# oresat-c3-v2.net
KiCad netlist of a schematic drawn in EAGLE
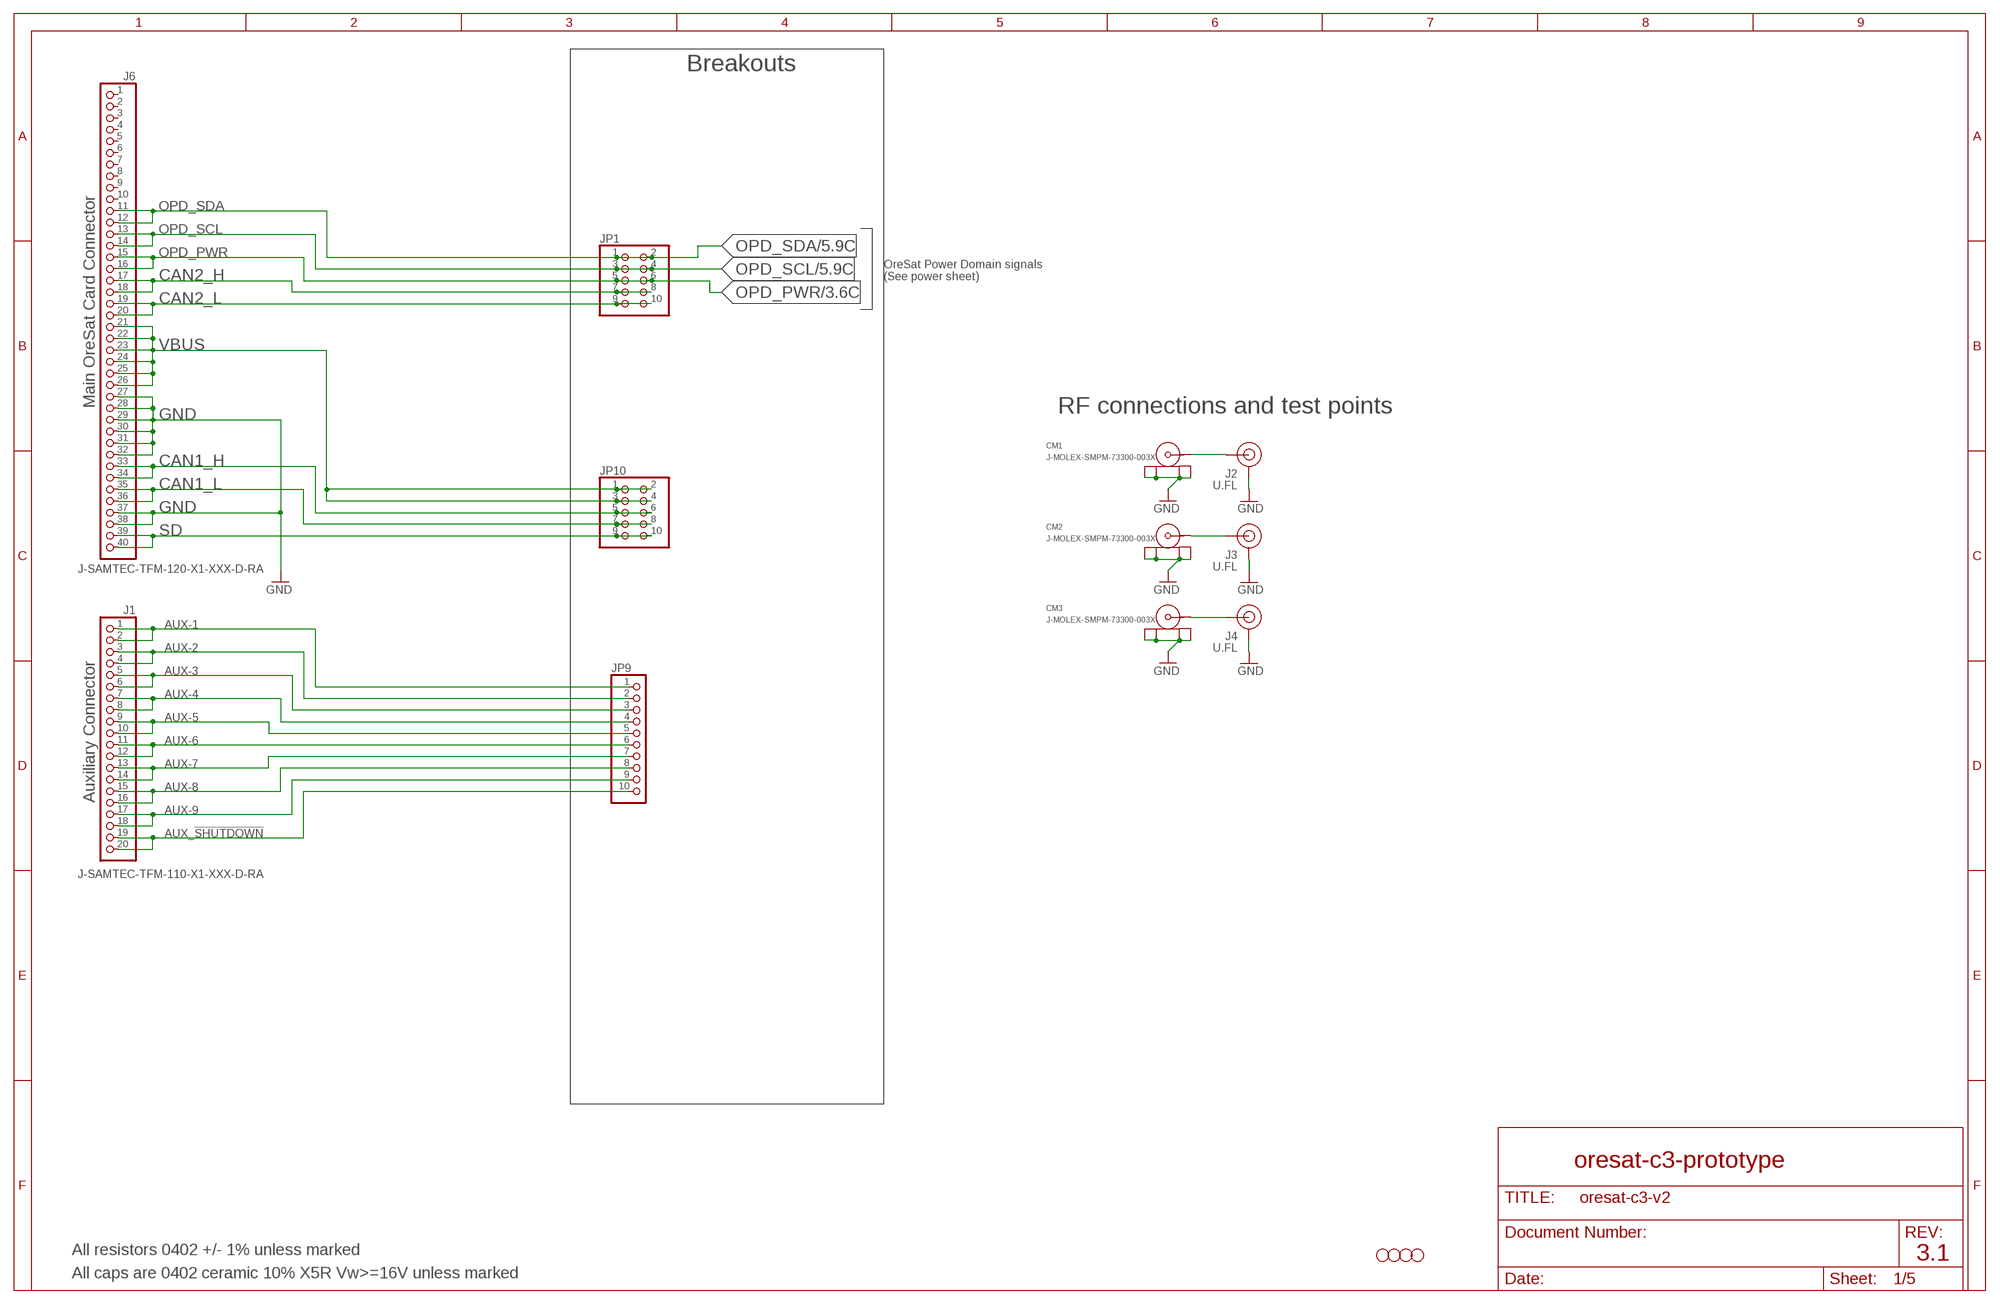
[diagram p0: schematic, sheet 1]
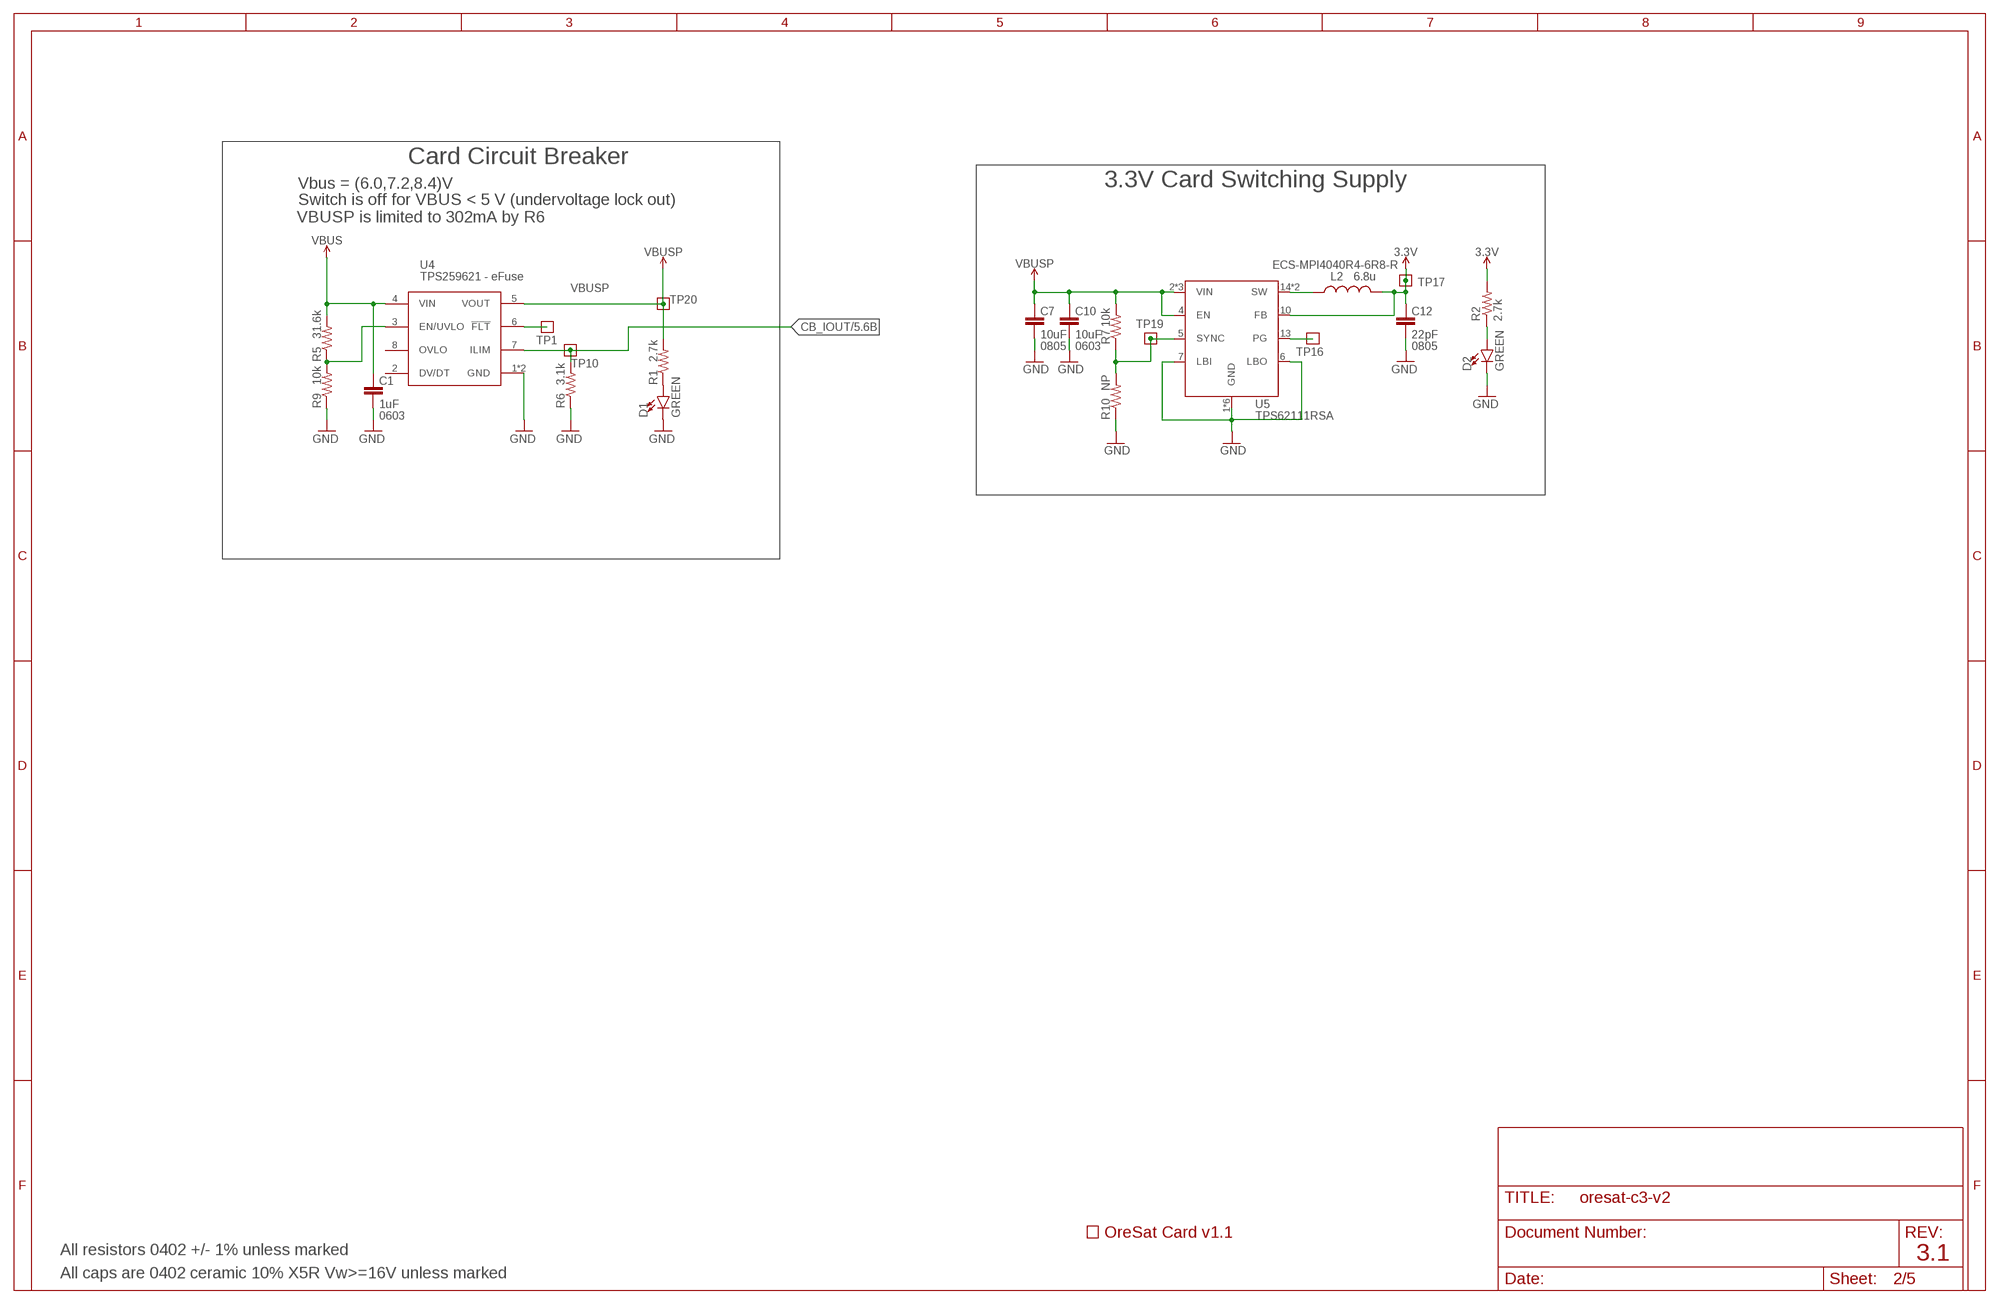
[diagram p1: schematic, sheet 2]
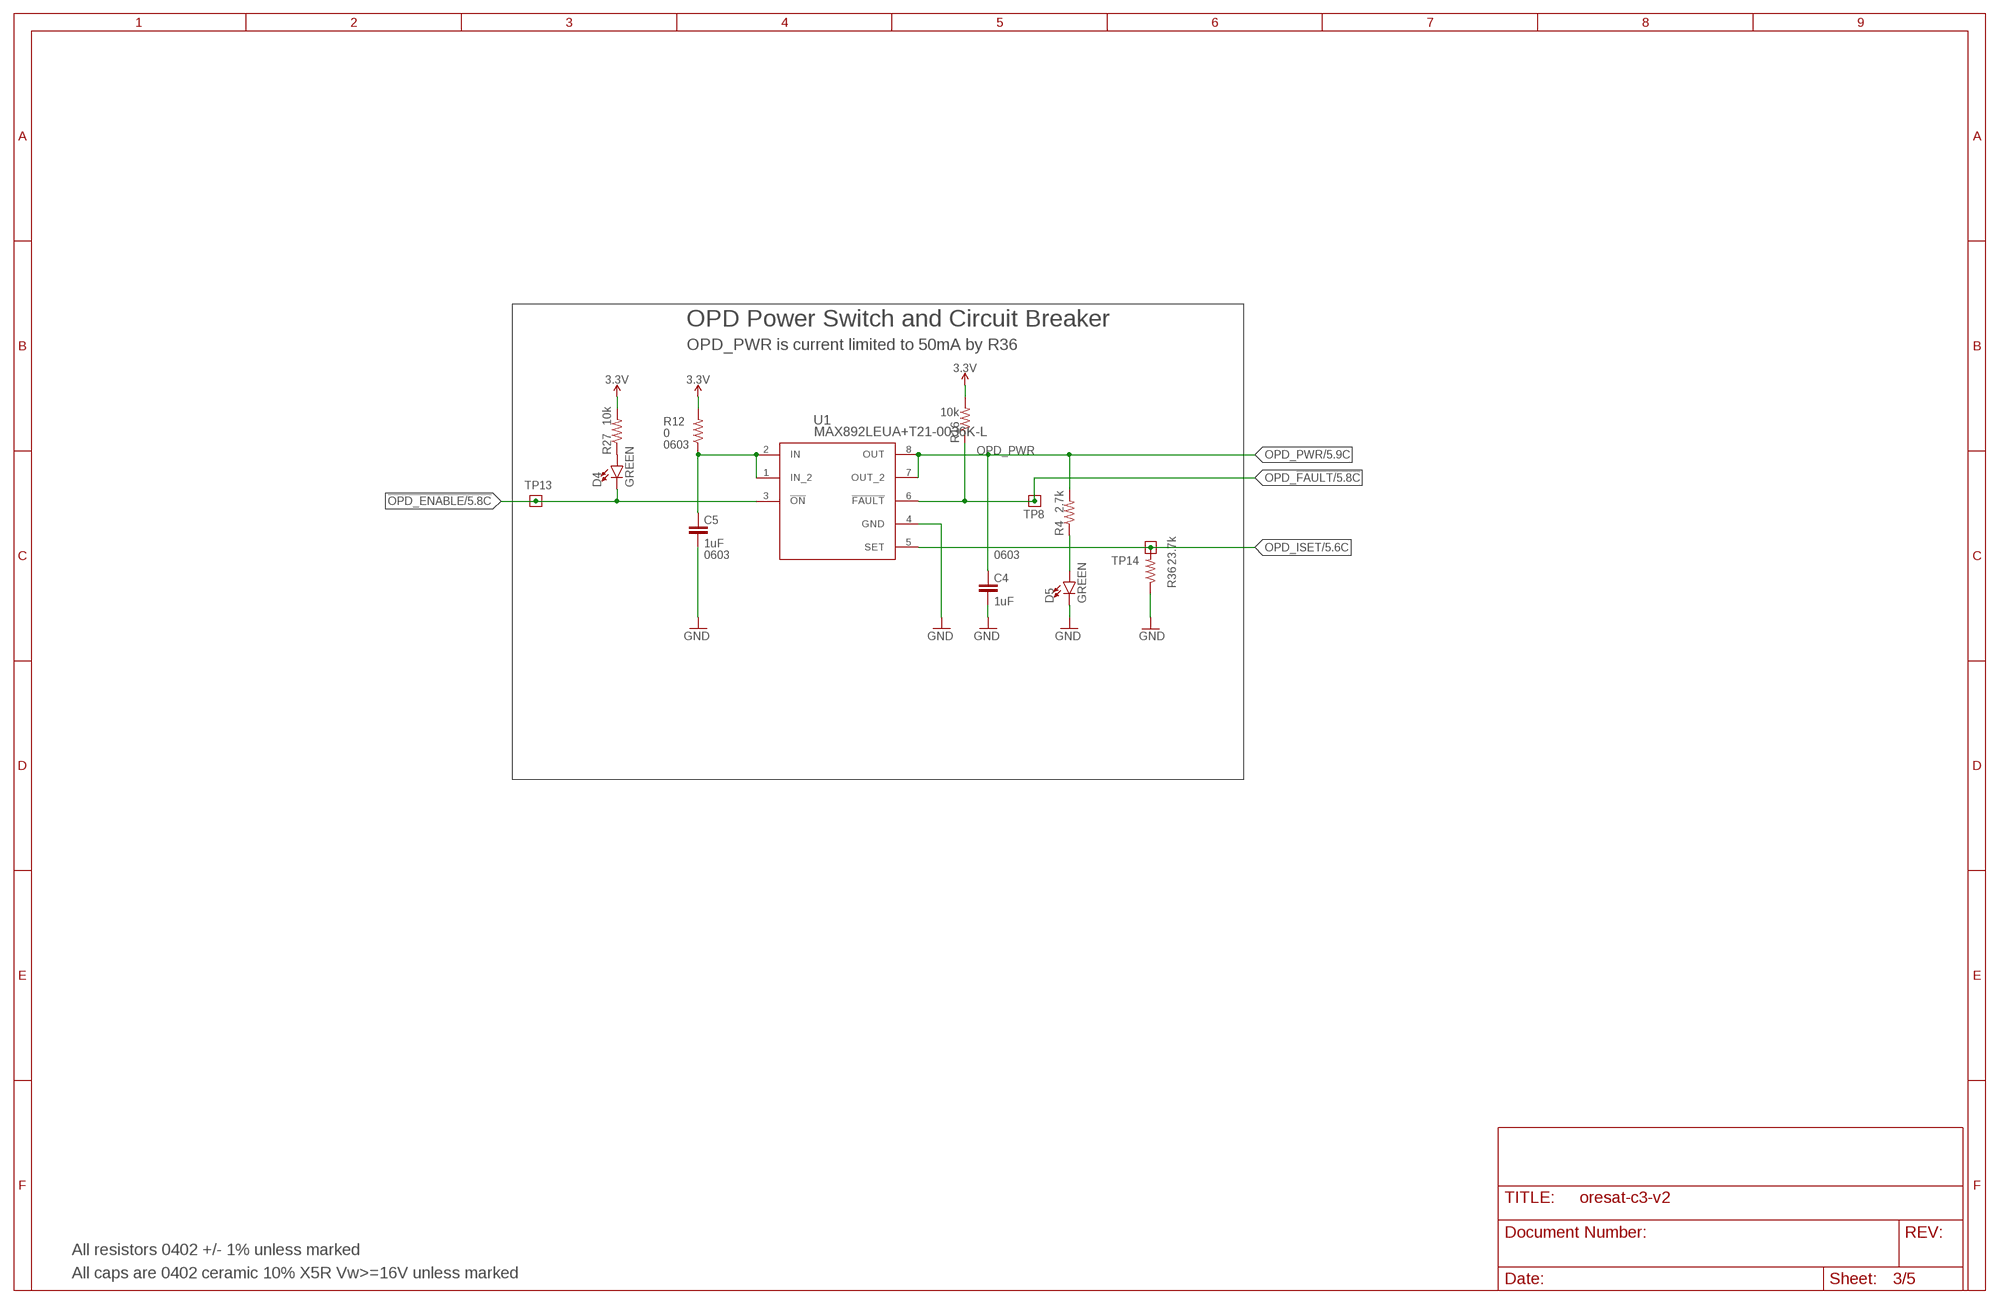
[diagram p2: schematic, sheet 3]
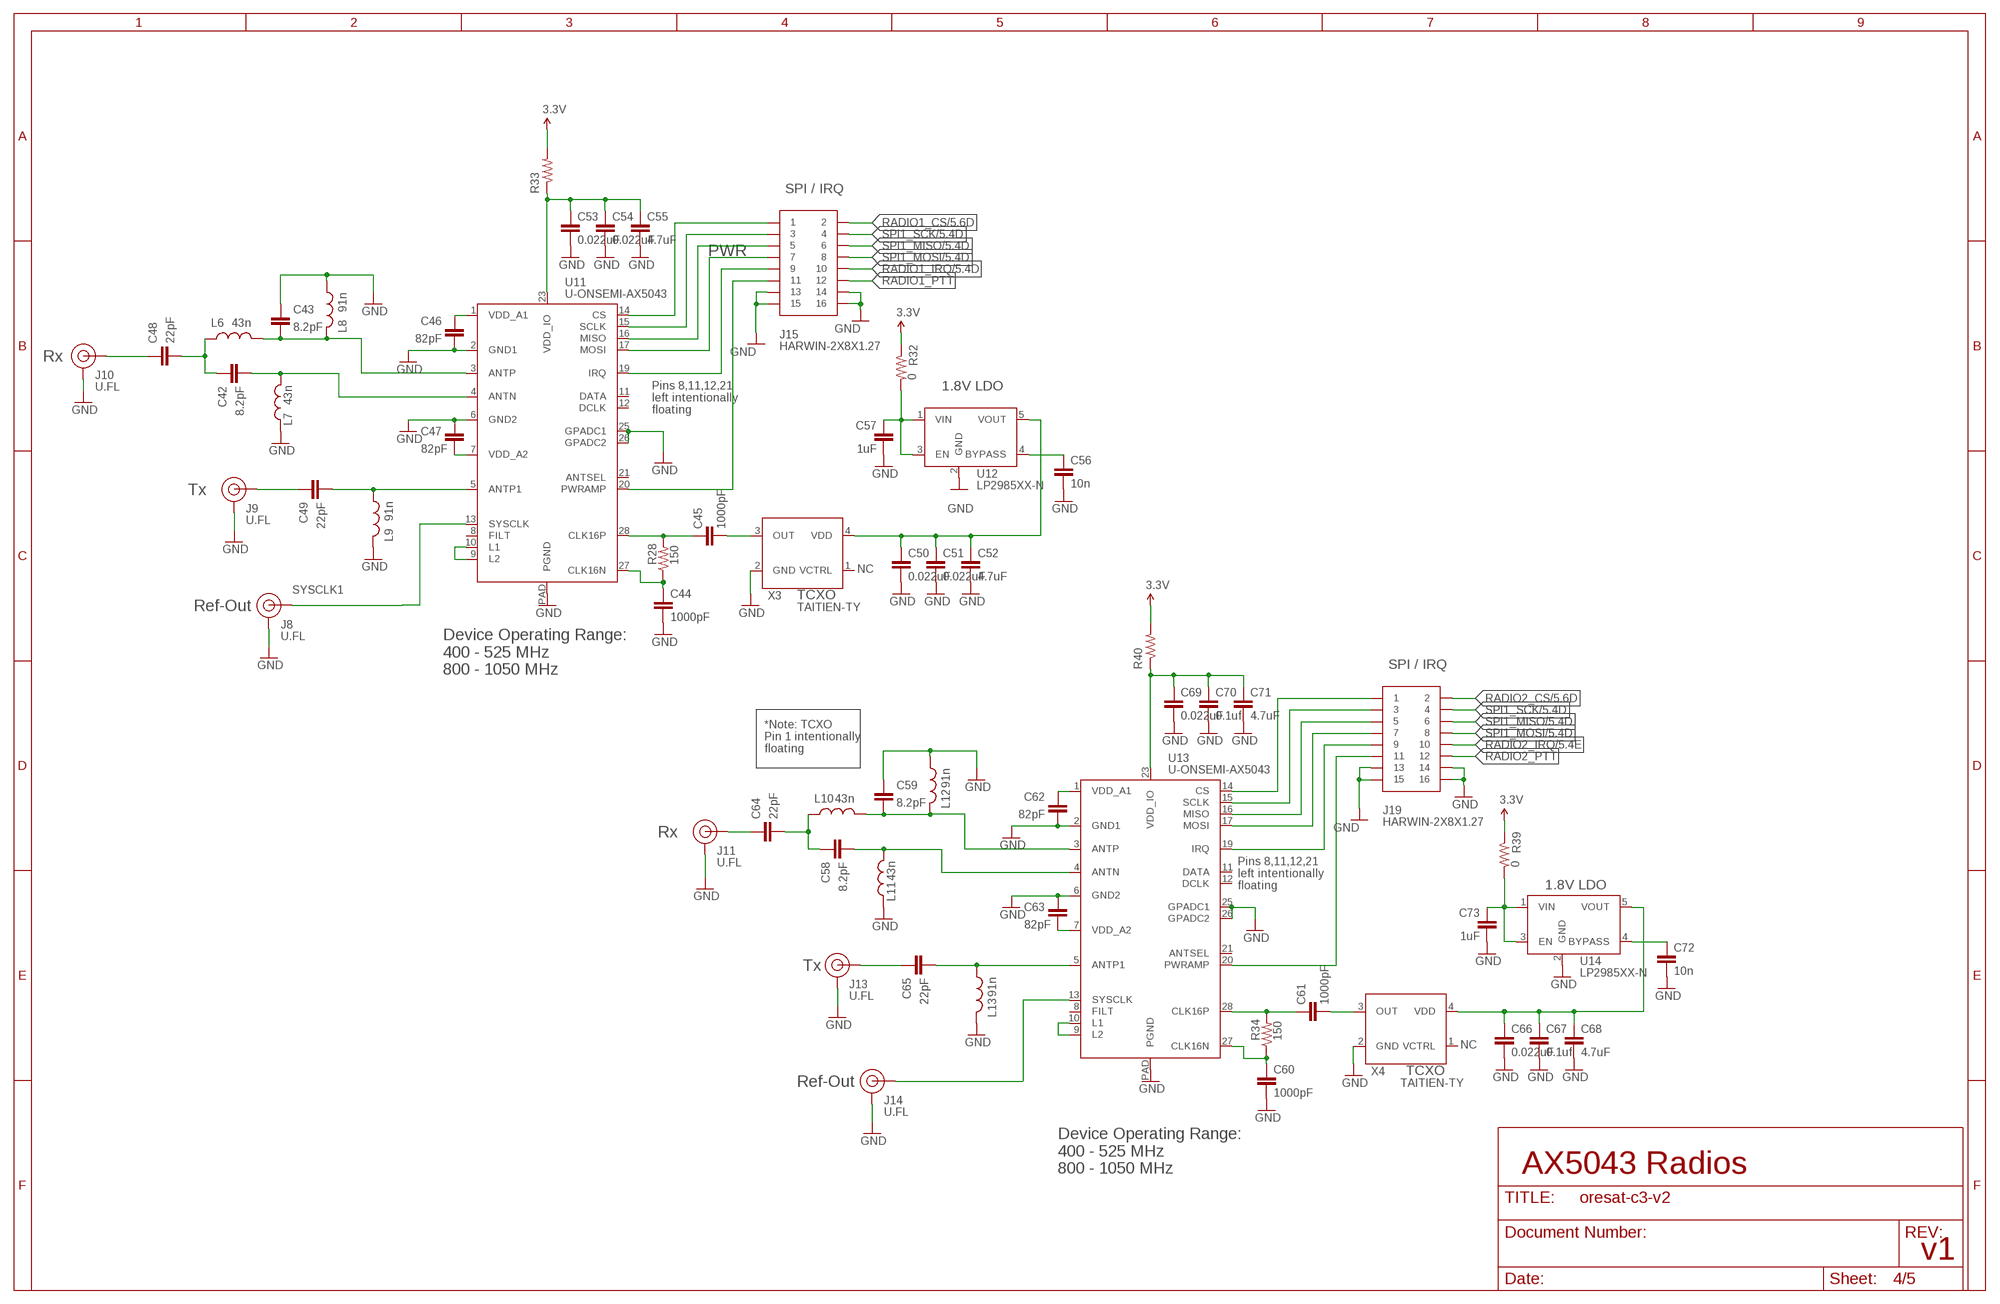
[diagram p3: schematic, sheet 4]
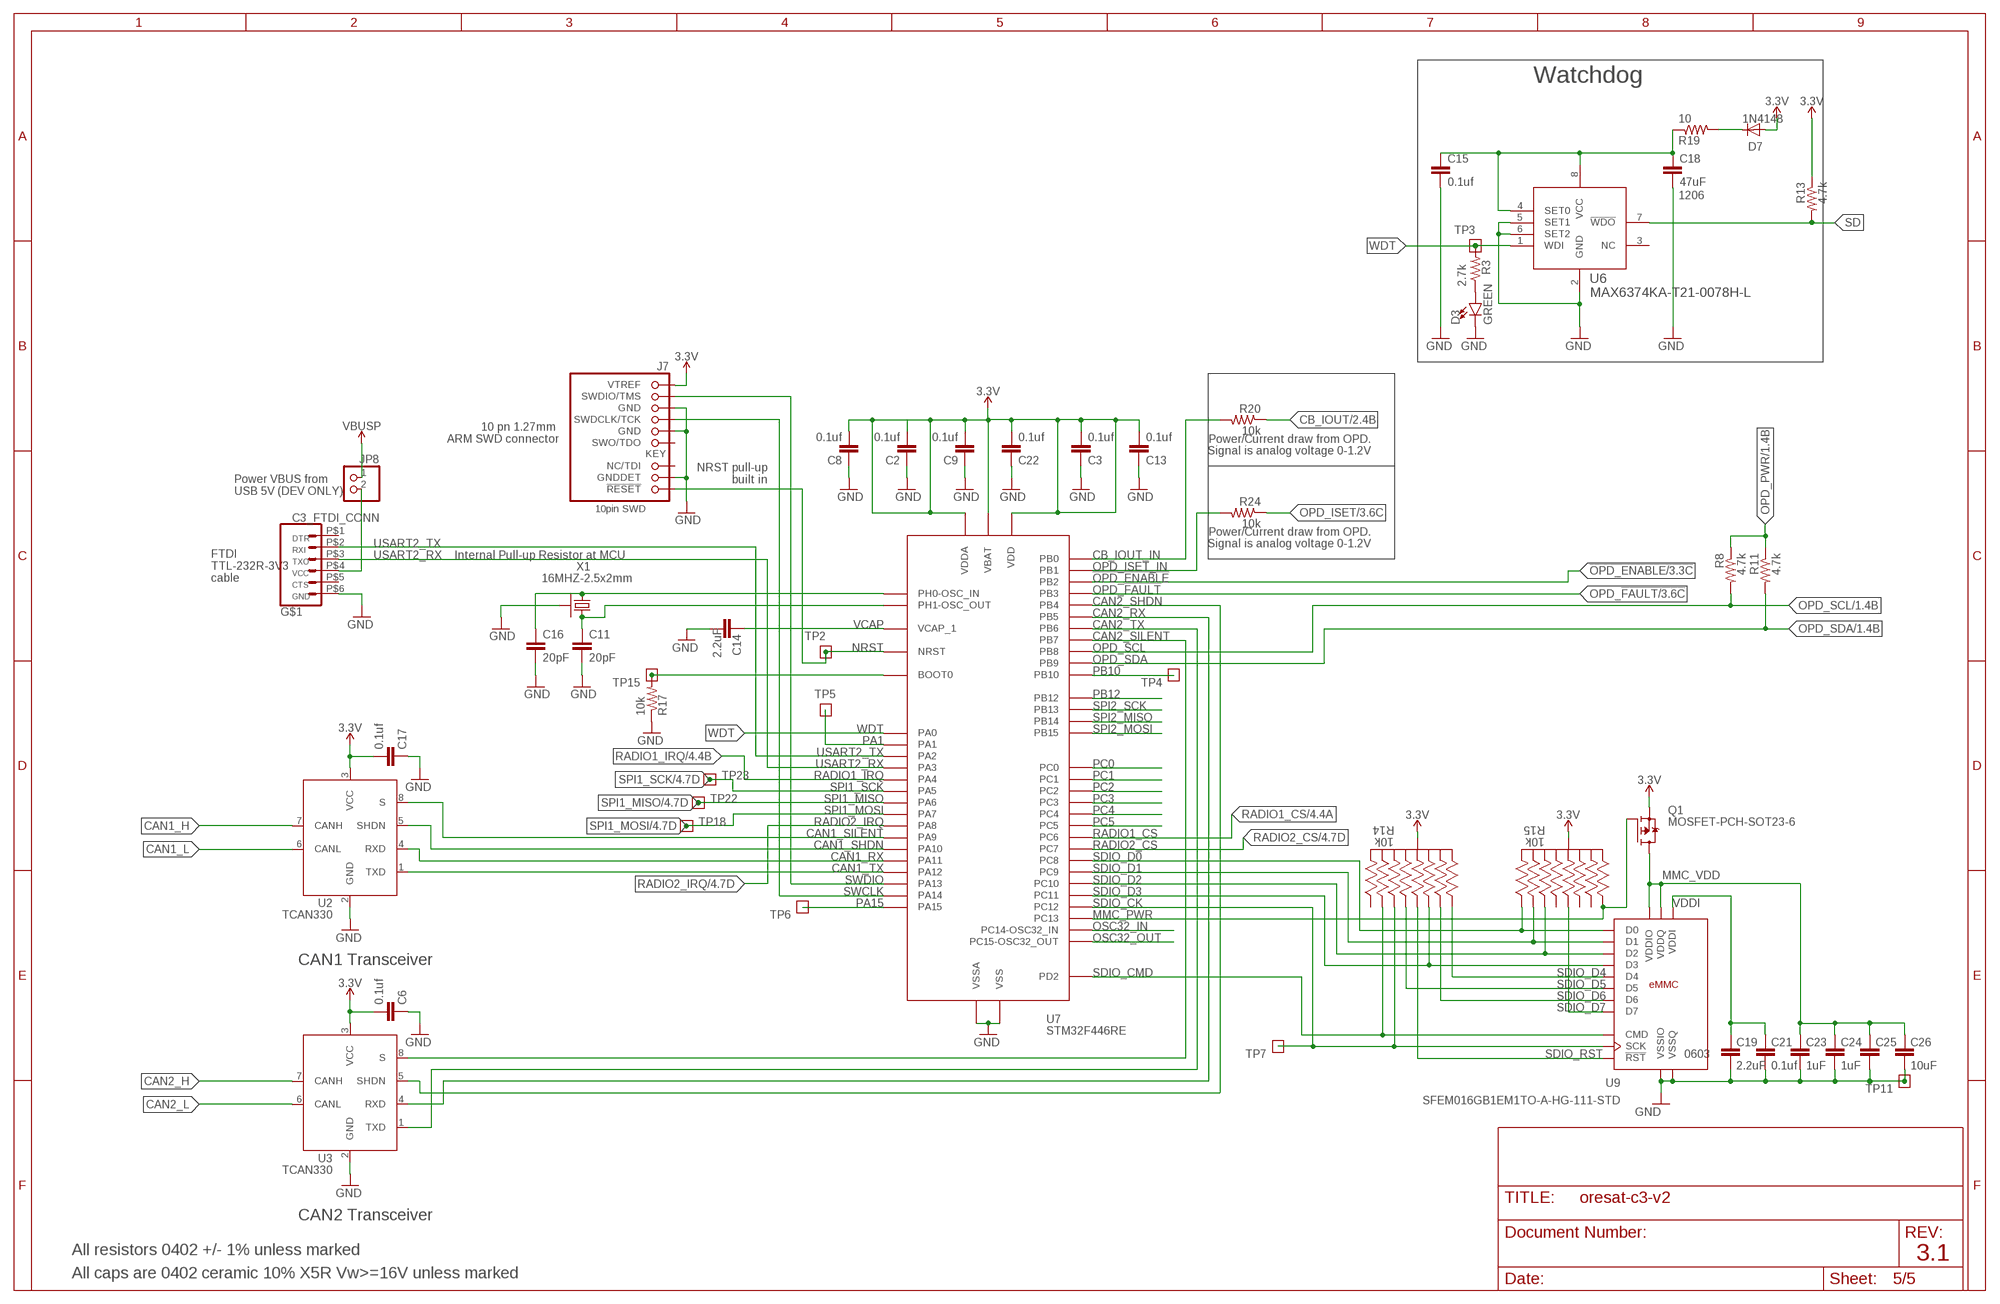
[diagram p4: schematic, sheet 5]

(export (version "E")
  (design (tool "Eeschema 10.0.6"))
  (components
    (comp (ref "C2")
      (value "0.1uf")
      (footprint "eagle-import:.0603-B-NOSILK")
      (fields
        (field (name "MANUFACTURER_PART_NUMBER") "0603ZD104KAT2A")
        (field (name "MOUSER_PART_NUMBER") "581-0603ZD104KAT2A")
        (field (name "MFR") "Samsung")
      )
      (libsource (lib "eagle-import") (part "CAP0603-0.1UF"))
    )
    (comp (ref "C3")
      (value "0.1uf")
      (footprint "eagle-import:.0603-B-NOSILK")
      (fields
        (field (name "MANUFACTURER_PART_NUMBER") "0603ZD104KAT2A")
        (field (name "MOUSER_PART_NUMBER") "581-0603ZD104KAT2A")
        (field (name "MFR") "Samsung")
      )
      (libsource (lib "eagle-import") (part "CAP0603-0.1UF"))
    )
    (comp (ref "C6")
      (value "0.1uf")
      (footprint "eagle-import:.0603-B-NOSILK")
      (fields
        (field (name "MANUFACTURER_PART_NUMBER") "0603ZD104KAT2A")
        (field (name "MOUSER_PART_NUMBER") "581-0603ZD104KAT2A")
        (field (name "MFR") "Samsung")
      )
      (libsource (lib "eagle-import") (part "CAP0603-0.1UF"))
    )
    (comp (ref "C8")
      (value "0.1uf")
      (footprint "eagle-import:.0603-B-NOSILK")
      (fields
        (field (name "MANUFACTURER_PART_NUMBER") "0603ZD104KAT2A")
        (field (name "MOUSER_PART_NUMBER") "581-0603ZD104KAT2A")
        (field (name "MFR") "Samsung")
      )
      (libsource (lib "eagle-import") (part "CAP0603-0.1UF"))
    )
    (comp (ref "C9")
      (value "0.1uf")
      (footprint "eagle-import:.0603-B-NOSILK")
      (fields
        (field (name "MANUFACTURER_PART_NUMBER") "0603ZD104KAT2A")
        (field (name "MOUSER_PART_NUMBER") "581-0603ZD104KAT2A")
        (field (name "MFR") "Samsung")
      )
      (libsource (lib "eagle-import") (part "CAP0603-0.1UF"))
    )
    (comp (ref "C11")
      (value "20pF")
      (footprint "eagle-import:.0603-B-NOSILK")
      (fields
        (field (name "MANUFACTURER_PART_NUMBER") "GRM1885C1H200JA01J")
        (field (name "MOUSER_PART_NUMBER") "81-GRM185C1H200JA01J")
        (field (name "MFR") "Samsung")
      )
      (libsource (lib "eagle-import") (part "CAP0603-20PF"))
    )
    (comp (ref "C13")
      (value "0.1uf")
      (footprint "eagle-import:.0603-B-NOSILK")
      (fields
        (field (name "MANUFACTURER_PART_NUMBER") "0603ZD104KAT2A")
        (field (name "MOUSER_PART_NUMBER") "581-0603ZD104KAT2A")
        (field (name "MFR") "Samsung")
      )
      (libsource (lib "eagle-import") (part "CAP0603-0.1UF"))
    )
    (comp (ref "C14")
      (value "2.2uF")
      (footprint "eagle-import:.0603-B-NOSILK")
      (fields
        (field (name "MANUFACTURER_PART_NUMBER") "C1608X7R1A225M080AC")
        (field (name "MOUSER_PART_NUMBER") "810-C1608X7R1A225M")
        (field (name "MFR") "Samsung")
      )
      (libsource (lib "eagle-import") (part "CAP0603-2.2UF"))
    )
    (comp (ref "C15")
      (value "0.1uf")
      (footprint "eagle-import:.0603-B-NOSILK")
      (fields
        (field (name "MANUFACTURER_PART_NUMBER") "0603ZD104KAT2A")
        (field (name "MOUSER_PART_NUMBER") "581-0603ZD104KAT2A")
        (field (name "MFR") "Samsung")
      )
      (libsource (lib "eagle-import") (part "CAP0603-0.1UF"))
    )
    (comp (ref "C16")
      (value "20pF")
      (footprint "eagle-import:.0603-B-NOSILK")
      (fields
        (field (name "MANUFACTURER_PART_NUMBER") "GRM1885C1H200JA01J")
        (field (name "MOUSER_PART_NUMBER") "81-GRM185C1H200JA01J")
        (field (name "MFR") "Samsung")
      )
      (libsource (lib "eagle-import") (part "CAP0603-20PF"))
    )
    (comp (ref "C17")
      (value "0.1uf")
      (footprint "eagle-import:.0603-B-NOSILK")
      (fields
        (field (name "MANUFACTURER_PART_NUMBER") "0603ZD104KAT2A")
        (field (name "MOUSER_PART_NUMBER") "581-0603ZD104KAT2A")
        (field (name "MFR") "Samsung")
      )
      (libsource (lib "eagle-import") (part "CAP0603-0.1UF"))
    )
    (comp (ref "C18")
      (value "47uF")
      (footprint "eagle-import:.0603-B-NOSILK")
      (fields
        (field (name "MANUFACTURER_PART_NUMBER") "GRM188R60J476ME15D")
        (field (name "MOUSER_PART_NUMBER") "81-GRM188R60J476ME5D")
        (field (name "RS_PART_NUMBER") "1726834P")
      )
      (libsource (lib "eagle-import") (part "CAP0603-47UF"))
    )
    (comp (ref "C19")
      (value "2.2uF")
      (footprint "eagle-import:.0603-B-NOSILK")
      (fields
        (field (name "MANUFACTURER_PART_NUMBER") "C1608X7R1A225M080AC")
        (field (name "MOUSER_PART_NUMBER") "810-C1608X7R1A225M")
        (field (name "MFR") "Samsung")
      )
      (libsource (lib "eagle-import") (part "CAP0603-2.2UF"))
    )
    (comp (ref "C21")
      (value "0.1uf")
      (footprint "eagle-import:.0603-B-NOSILK")
      (fields
        (field (name "MANUFACTURER_PART_NUMBER") "0603ZD104KAT2A")
        (field (name "MOUSER_PART_NUMBER") "581-0603ZD104KAT2A")
        (field (name "MFR") "Samsung")
      )
      (libsource (lib "eagle-import") (part "CAP0603-0.1UF"))
    )
    (comp (ref "C22")
      (value "0.1uf")
      (footprint "eagle-import:.0603-B-NOSILK")
      (fields
        (field (name "MANUFACTURER_PART_NUMBER") "0603ZD104KAT2A")
        (field (name "MOUSER_PART_NUMBER") "581-0603ZD104KAT2A")
        (field (name "MFR") "Samsung")
      )
      (libsource (lib "eagle-import") (part "CAP0603-0.1UF"))
    )
    (comp (ref "C23")
      (value "1uF")
      (footprint "eagle-import:.0603-B-NOSILK")
      (fields
        (field (name "MANUFACTURER_PART_NUMBER") "0603X105K100CT")
        (field (name "MOUSER_PART_NUMBER") "791-0603X105K100CT")
        (field (name "MFR") "Samsung")
      )
      (libsource (lib "eagle-import") (part "CAP0603-1UF"))
    )
    (comp (ref "C24")
      (value "1uF")
      (footprint "eagle-import:.0603-B-NOSILK")
      (fields
        (field (name "MANUFACTURER_PART_NUMBER") "0603X105K100CT")
        (field (name "MOUSER_PART_NUMBER") "791-0603X105K100CT")
        (field (name "MFR") "Samsung")
      )
      (libsource (lib "eagle-import") (part "CAP0603-1UF"))
    )
    (comp (ref "C25")
      (value "1uF")
      (footprint "eagle-import:.0603-B-NOSILK")
      (fields
        (field (name "MANUFACTURER_PART_NUMBER") "0603X105K100CT")
        (field (name "MOUSER_PART_NUMBER") "791-0603X105K100CT")
        (field (name "MFR") "Samsung")
      )
      (libsource (lib "eagle-import") (part "CAP0603-1UF"))
    )
    (comp (ref "C26")
      (value "10uF")
      (footprint "eagle-import:.0603-B-NOSILK")
      (fields
        (field (name "MANUFACTURER_PART_NUMBER") "0603ZD106KAT2A")
        (field (name "MOUSER_PART_NUMBER") "581-0603ZD106KAT2A")
        (field (name "MFR") "Samsung")
      )
      (libsource (lib "eagle-import") (part "CAP0603-10UF"))
    )
    (comp (ref "D3")
      (value "GREEN")
      (footprint "eagle-import:LED-0603")
      (libsource (lib "eagle-import") (part "LED-GREEN0603"))
    )
    (comp (ref "D7")
      (value "1N4148")
      (footprint "eagle-import:SOD-323")
      (libsource (lib "eagle-import") (part "DIODESOD"))
    )
    (comp (ref "J7")
      (value "FTSH-105-XX-X-DV-K")
      (footprint "eagle-import:CON10_2X5_DUK_FTSH")
      (fields (field (name "MFR") "Samtec") (field (name "MPN") "FTSH-105-01-F-DV-K"))
      (libsource (lib "eagle-import") (part "FTSH-105-XX-X-DV-K"))
    )
    (comp (ref "JP8")
      (value "PINHD-1X2")
      (footprint "eagle-import:1X02")
      (libsource (lib "eagle-import") (part "PINHD-1X2"))
    )
    (comp (ref "Q1")
      (value "MOSFET-PCH-SOT23-6")
      (footprint "eagle-import:SOT23-6")
      (libsource (lib "eagle-import") (part "MOSFET-PCH-SOT23-6"))
    )
    (comp (ref "R3")
      (value "2.7k")
      (footprint "eagle-import:.0603-C-NOSILK")
      (fields
        (field (name "MANUFACTURER_PART_NUMBER") "CR0603-FX-2701ELF")
        (field (name "MOUSER_PART_NUMBER") "652-CR0603-FX2701ELF")
        (field (name "MFR") "Samsung")
      )
      (libsource (lib "eagle-import") (part "R0603-2.7K-OHMS"))
    )
    (comp (ref "R8")
      (value "4.7k")
      (footprint "eagle-import:.0603-C-NOSILK")
      (fields
        (field (name "MANUFACTURER_PART_NUMBER") "CR0603-FX-4701ELF")
        (field (name "MOUSER_PART_NUMBER") "652-CR0603FX-4701ELF")
        (field (name "RS_PART_NUMBER") "7408877P")
      )
      (libsource (lib "eagle-import") (part "R0603-4.7K-OHMS"))
    )
    (comp (ref "R11")
      (value "4.7k")
      (footprint "eagle-import:.0603-C-NOSILK")
      (fields
        (field (name "MANUFACTURER_PART_NUMBER") "CR0603-FX-4701ELF")
        (field (name "MOUSER_PART_NUMBER") "652-CR0603FX-4701ELF")
        (field (name "RS_PART_NUMBER") "7408877P")
      )
      (libsource (lib "eagle-import") (part "R0603-4.7K-OHMS"))
    )
    (comp (ref "R13")
      (value "4.7k")
      (footprint "eagle-import:.0603-C-NOSILK")
      (fields
        (field (name "MANUFACTURER_PART_NUMBER") "CR0603-FX-4701ELF")
        (field (name "MOUSER_PART_NUMBER") "652-CR0603FX-4701ELF")
        (field (name "RS_PART_NUMBER") "7408877P")
      )
      (libsource (lib "eagle-import") (part "R0603-4.7K-OHMS"))
    )
    (comp (ref "R14")
      (value "10k")
      (footprint "eagle-import:ARRAY_EXBA-M")
      (fields (field (name "MANUFACTURER_PART_NUMBER") "EXBA10P391J"))
      (libsource (lib "eagle-import") (part "EXB-A10P391JC_ARRAY_EXBA-M"))
    )
    (comp (ref "R15")
      (value "10k")
      (footprint "eagle-import:ARRAY_EXBA-M")
      (fields (field (name "MANUFACTURER_PART_NUMBER") "EXBA10P391J"))
      (libsource (lib "eagle-import") (part "EXB-A10P391JC_ARRAY_EXBA-M"))
    )
    (comp (ref "R17")
      (value "10k")
      (footprint "eagle-import:.0603-C-NOSILK")
      (fields
        (field (name "MANUFACTURER_PART_NUMBER") "CR0603-FX-1002ELF")
        (field (name "MOUSER_PART_NUMBER") "652-CR0603FX-1002ELF")
        (field (name "RS_PART_NUMBER") "7408805P")
      )
      (libsource (lib "eagle-import") (part "R0603-10K-OHMS"))
    )
    (comp (ref "R19")
      (value "10")
      (footprint "eagle-import:.0603-C-NOSILK")
      (fields
        (field (name "MANUFACTURER_PART_NUMBER") "CR0603-FX-10R0ELF")
        (field (name "MOUSER_PART_NUMBER") "652-CR0603FX-10R0ELF")
        (field (name "RS_PART_NUMBER") "7408818P")
      )
      (libsource (lib "eagle-import") (part "R0603-10-OHMS"))
    )
    (comp (ref "R20")
      (value "10k")
      (footprint "eagle-import:.0603-C-NOSILK")
      (fields
        (field (name "MANUFACTURER_PART_NUMBER") "CR0603-FX-1002ELF")
        (field (name "MOUSER_PART_NUMBER") "652-CR0603FX-1002ELF")
        (field (name "RS_PART_NUMBER") "7408805P")
      )
      (libsource (lib "eagle-import") (part "R0603-10K-OHMS"))
    )
    (comp (ref "R24")
      (value "10k")
      (footprint "eagle-import:.0603-C-NOSILK")
      (fields
        (field (name "MANUFACTURER_PART_NUMBER") "CR0603-FX-1002ELF")
        (field (name "MOUSER_PART_NUMBER") "652-CR0603FX-1002ELF")
        (field (name "RS_PART_NUMBER") "7408805P")
      )
      (libsource (lib "eagle-import") (part "R0603-10K-OHMS"))
    )
    (comp (ref "TP2")
      (value "TEST-POINT")
      (footprint "eagle-import:2MM-TEST-POINT")
      (libsource (lib "eagle-import") (part "TEST-POINT"))
    )
    (comp (ref "TP3")
      (value "TEST-POINT")
      (footprint "eagle-import:2MM-TEST-POINT")
      (libsource (lib "eagle-import") (part "TEST-POINT"))
    )
    (comp (ref "TP4")
      (value "TEST-POINT")
      (footprint "eagle-import:2MM-TEST-POINT")
      (libsource (lib "eagle-import") (part "TEST-POINT"))
    )
    (comp (ref "TP5")
      (value "TEST-POINT")
      (footprint "eagle-import:2MM-TEST-POINT")
      (libsource (lib "eagle-import") (part "TEST-POINT"))
    )
    (comp (ref "TP6")
      (value "TEST-POINT")
      (footprint "eagle-import:2MM-TEST-POINT")
      (libsource (lib "eagle-import") (part "TEST-POINT"))
    )
    (comp (ref "TP7")
      (value "TEST-POINT")
      (footprint "eagle-import:2MM-TEST-POINT")
      (libsource (lib "eagle-import") (part "TEST-POINT"))
    )
    (comp (ref "TP11")
      (value "TEST-POINT")
      (footprint "eagle-import:2MM-TEST-POINT")
      (libsource (lib "eagle-import") (part "TEST-POINT"))
    )
    (comp (ref "TP15")
      (value "TEST-POINT")
      (footprint "eagle-import:2MM-TEST-POINT")
      (libsource (lib "eagle-import") (part "TEST-POINT"))
    )
    (comp (ref "TP18")
      (value "TEST-POINT")
      (footprint "eagle-import:2MM-TEST-POINT")
      (libsource (lib "eagle-import") (part "TEST-POINT"))
    )
    (comp (ref "TP22")
      (value "TEST-POINT")
      (footprint "eagle-import:2MM-TEST-POINT")
      (libsource (lib "eagle-import") (part "TEST-POINT"))
    )
    (comp (ref "TP23")
      (value "TEST-POINT")
      (footprint "eagle-import:2MM-TEST-POINT")
      (libsource (lib "eagle-import") (part "TEST-POINT"))
    )
    (comp (ref "U$2")
      (value "C3_FTDI_CONN")
      (footprint "eagle-import:6_PIN_SERIAL_TARGET_SIDE_W_SILK")
      (libsource (lib "eagle-import") (part "C3_FTDI_CONN"))
    )
    (comp (ref "U2")
      (value "TCAN330")
      (footprint "eagle-import:SOT23-8_TI-DCN")
      (fields (field (name "MFR") "Texas Instruments") (field (name "MPN") "TCAN330GDCNT"))
      (libsource (lib "eagle-import") (part "TCAN330"))
    )
    (comp (ref "U3")
      (value "TCAN330")
      (footprint "eagle-import:SOT23-8_TI-DCN")
      (fields (field (name "MFR") "Texas Instruments") (field (name "MPN") "TCAN330GDCNT"))
      (libsource (lib "eagle-import") (part "TCAN330"))
    )
    (comp (ref "U6")
      (value "MAX6374KA-T21-0078H-L")
      (footprint "eagle-import:21-0078H-L")
      (fields (field (name "MANUFACTURER_PART_NUMBER") "max6374kat"))
      (libsource (lib "eagle-import") (part "MAX6374KA-T21-0078H-L"))
    )
    (comp (ref "U7")
      (value "STM32F446RE")
      (footprint "eagle-import:QFP-10X10-64")
      (libsource (lib "eagle-import") (part "STM32F446RE"))
    )
    (comp (ref "U9")
      (value "SFEM016GB1EM1TO-A-HG-111-STD")
      (footprint "eagle-import:BGA-153(11.5X13)(EMMC-BA)")
      (libsource (lib "eagle-import") (part "EMMC+RESET-BA"))
    )
    (comp (ref "X1")
      (value "16MHZ-2.5x2mm")
      (footprint "eagle-import:CRYSTAL_2.5X2")
      (fields (field (name "MFR") "ECS Inc.") (field (name "MPN") "ECS-160-10-36Q-ES-TR"))
      (libsource (lib "eagle-import") (part "CRYSTAL-WITH-GND"))
    )
    (comp (ref "CM1")
      (value "J-MOLEX-SMPM-73300-003X")
      (footprint "eagle-import:J-MOLEX-SMPM-073300-003X")
      (fields (field (name "MFR") "Molex") (field (name "MPN") "73300-0020"))
      (libsource (lib "eagle-import") (part "J-MOLEX-SMPM-73300-003X"))
    )
    (comp (ref "CM2")
      (value "J-MOLEX-SMPM-73300-003X")
      (footprint "eagle-import:J-MOLEX-SMPM-073300-003X")
      (fields (field (name "MFR") "Molex") (field (name "MPN") "73300-0020"))
      (libsource (lib "eagle-import") (part "J-MOLEX-SMPM-73300-003X"))
    )
    (comp (ref "CM3")
      (value "J-MOLEX-SMPM-73300-003X")
      (footprint "eagle-import:J-MOLEX-SMPM-073300-003X")
      (fields (field (name "MFR") "Molex") (field (name "MPN") "73300-0020"))
      (libsource (lib "eagle-import") (part "J-MOLEX-SMPM-73300-003X"))
    )
    (comp (ref "H1")
      (value "STAND-OFFTIGHT")
      (footprint "eagle-import:STAND-OFF-TIGHT")
      (libsource (lib "eagle-import") (part "STAND-OFFTIGHT"))
    )
    (comp (ref "H2")
      (value "STAND-OFFTIGHT")
      (footprint "eagle-import:STAND-OFF-TIGHT")
      (libsource (lib "eagle-import") (part "STAND-OFFTIGHT"))
    )
    (comp (ref "H3")
      (value "STAND-OFFTIGHT")
      (footprint "eagle-import:STAND-OFF-TIGHT")
      (libsource (lib "eagle-import") (part "STAND-OFFTIGHT"))
    )
    (comp (ref "H4")
      (value "STAND-OFFTIGHT")
      (footprint "eagle-import:STAND-OFF-TIGHT")
      (libsource (lib "eagle-import") (part "STAND-OFFTIGHT"))
    )
    (comp (ref "J1")
      (value "J-SAMTEC-TFM-110-X1-XXX-D-RA")
      (footprint "eagle-import:J-SAMTEC-TFM-110-X1-XXX-D-RA")
      (fields (field (name "MFR") "Samtec") (field (name "MPN") "TFM-110-01-L-D-RA "))
      (libsource (lib "eagle-import") (part "J-SAMTEC-TFM-110-X1-XXX-D-RA"))
    )
    (comp (ref "J2")
      (value "U.FL")
      (footprint "eagle-import:U.FL")
      (libsource (lib "eagle-import") (part "U.FL2PIN"))
    )
    (comp (ref "J3")
      (value "U.FL")
      (footprint "eagle-import:U.FL")
      (libsource (lib "eagle-import") (part "U.FL2PIN"))
    )
    (comp (ref "J4")
      (value "U.FL")
      (footprint "eagle-import:U.FL")
      (libsource (lib "eagle-import") (part "U.FL2PIN"))
    )
    (comp (ref "J6")
      (value "J-SAMTEC-TFM-120-X1-XXX-D-RA")
      (footprint "eagle-import:J-SAMTEC-TFM-120-X1-XXX-D-RA")
      (fields (field (name "MFR") "Samtec") (field (name "MPN") "TFM-120-01-L-D-RA"))
      (libsource (lib "eagle-import") (part "J-SAMTEC-TFM-120-X1-XXX-D-RA"))
    )
    (comp (ref "JP1")
      (value "PINHD-2X5")
      (footprint "eagle-import:2X05")
      (libsource (lib "eagle-import") (part "PINHD-2X5"))
    )
    (comp (ref "JP9")
      (value "PINHD-1X10")
      (footprint "eagle-import:1X10")
      (libsource (lib "eagle-import") (part "PINHD-1X10"))
    )
    (comp (ref "JP10")
      (value "PINHD-2X5")
      (footprint "eagle-import:2X05")
      (libsource (lib "eagle-import") (part "PINHD-2X5"))
    )
    (comp (ref "C4")
      (value "1uF")
      (footprint "eagle-import:.0603-B-NOSILK")
      (fields
        (field (name "MANUFACTURER_PART_NUMBER") "0603X105K100CT")
        (field (name "MOUSER_PART_NUMBER") "791-0603X105K100CT")
        (field (name "MFR") "Samsung")
      )
      (libsource (lib "eagle-import") (part "CAP0603-1UF"))
    )
    (comp (ref "C5")
      (value "1uF")
      (footprint "eagle-import:.0603-B-NOSILK")
      (fields
        (field (name "MANUFACTURER_PART_NUMBER") "0603X105K100CT")
        (field (name "MOUSER_PART_NUMBER") "791-0603X105K100CT")
        (field (name "MFR") "Samsung")
      )
      (libsource (lib "eagle-import") (part "CAP0603-1UF"))
    )
    (comp (ref "D4")
      (value "GREEN")
      (footprint "eagle-import:LED-0603")
      (libsource (lib "eagle-import") (part "LED-GREEN0603"))
    )
    (comp (ref "D5")
      (value "GREEN")
      (footprint "eagle-import:LED-0603")
      (libsource (lib "eagle-import") (part "LED-GREEN0603"))
    )
    (comp (ref "R4")
      (value "2.7k")
      (footprint "eagle-import:.0603-C-NOSILK")
      (fields
        (field (name "MANUFACTURER_PART_NUMBER") "CR0603-FX-2701ELF")
        (field (name "MOUSER_PART_NUMBER") "652-CR0603-FX2701ELF")
        (field (name "MFR") "Samsung")
      )
      (libsource (lib "eagle-import") (part "R0603-2.7K-OHMS"))
    )
    (comp (ref "R12")
      (value "0")
      (footprint "eagle-import:.0603-C-NOSILK")
      (fields
        (field (name "MANUFACTURER_PART_NUMBER") "CRCW06030000Z0EAC")
        (field (name "MOUSER_PART_NUMBER") "71-CRCW06030000Z0EAC")
        (field (name "MFR") "Samsung")
      )
      (libsource (lib "eagle-import") (part "R0603-0-OHMS"))
    )
    (comp (ref "R16")
      (value "10k")
      (footprint "eagle-import:.0603-C-NOSILK")
      (fields
        (field (name "MANUFACTURER_PART_NUMBER") "CR0603-FX-1002ELF")
        (field (name "MOUSER_PART_NUMBER") "652-CR0603FX-1002ELF")
        (field (name "RS_PART_NUMBER") "7408805P")
      )
      (libsource (lib "eagle-import") (part "R0603-10K-OHMS"))
    )
    (comp (ref "R27")
      (value "10k")
      (footprint "eagle-import:.0603-C-NOSILK")
      (fields
        (field (name "MANUFACTURER_PART_NUMBER") "CR0603-FX-1002ELF")
        (field (name "MOUSER_PART_NUMBER") "652-CR0603FX-1002ELF")
        (field (name "RS_PART_NUMBER") "7408805P")
      )
      (libsource (lib "eagle-import") (part "R0603-10K-OHMS"))
    )
    (comp (ref "R36")
      (value "23.7k")
      (footprint "eagle-import:.0603-C-NOSILK")
      (fields
        (field (name "MANUFACTURER_PART_NUMBER") "CR0603-FX-2372ELF")
        (field (name "MOUSER_PART_NUMBER") "652-CR0603FX-2372ELF")
        (field (name "MFR") "Samsung")
      )
      (libsource (lib "eagle-import") (part "R0603-23.7K-OHMS"))
    )
    (comp (ref "TP8")
      (value "TEST-POINT")
      (footprint "eagle-import:2MM-TEST-POINT")
      (libsource (lib "eagle-import") (part "TEST-POINT"))
    )
    (comp (ref "TP13")
      (value "TEST-POINT")
      (footprint "eagle-import:2MM-TEST-POINT")
      (libsource (lib "eagle-import") (part "TEST-POINT"))
    )
    (comp (ref "TP14")
      (value "TEST-POINT")
      (footprint "eagle-import:2MM-TEST-POINT")
      (libsource (lib "eagle-import") (part "TEST-POINT"))
    )
    (comp (ref "U1")
      (value "MAX892LEUA+T21-0036K-L")
      (footprint "eagle-import:21-0036K-L")
      (fields (field (name "MANUFACTURER_PART_NUMBER") "MAX892LEUA+T"))
      (libsource (lib "eagle-import") (part "MAX892LEUA+T21-0036K-L"))
    )
    (comp (ref "C1")
      (value "1uF")
      (footprint "eagle-import:.0603-B-NOSILK")
      (fields
        (field (name "MANUFACTURER_PART_NUMBER") "0603X105K100CT")
        (field (name "MOUSER_PART_NUMBER") "791-0603X105K100CT")
        (field (name "MFR") "Samsung")
      )
      (libsource (lib "eagle-import") (part "CAP0603-1UF"))
    )
    (comp (ref "C7")
      (value "10uF")
      (footprint "eagle-import:.0603-B-NOSILK")
      (fields
        (field (name "MANUFACTURER_PART_NUMBER") "0603ZD106KAT2A")
        (field (name "MOUSER_PART_NUMBER") "581-0603ZD106KAT2A")
      )
      (libsource (lib "eagle-import") (part "CAP0603-10UF"))
    )
    (comp (ref "C10")
      (value "10uF")
      (footprint "eagle-import:.0603-B-NOSILK")
      (fields
        (field (name "MANUFACTURER_PART_NUMBER") "0603ZD106KAT2A")
        (field (name "MOUSER_PART_NUMBER") "581-0603ZD106KAT2A")
        (field (name "MFR") "Samsung")
      )
      (libsource (lib "eagle-import") (part "CAP0603-10UF"))
    )
    (comp (ref "C12")
      (value "22pF")
      (footprint "eagle-import:.0603-B-NOSILK")
      (fields
        (field (name "MANUFACTURER_PART_NUMBER") "06035A220JAT4A")
        (field (name "MOUSER_PART_NUMBER") "581-06035A220JAT4A")
      )
      (libsource (lib "eagle-import") (part "CAP0603-22PF"))
    )
    (comp (ref "D1")
      (value "GREEN")
      (footprint "eagle-import:LED-0603")
      (libsource (lib "eagle-import") (part "LED-GREEN0603"))
    )
    (comp (ref "D2")
      (value "GREEN")
      (footprint "eagle-import:LED-0603")
      (libsource (lib "eagle-import") (part "LED-GREEN0603"))
    )
    (comp (ref "L2")
      (value "6.8u")
      (footprint "eagle-import:ECS-MPI4040")
      (fields (field (name "MFR") "ECS") (field (name "MPN") "ECS-MPI4040R4-6R8-R"))
      (libsource (lib "eagle-import") (part "L-ECS-MPI4040"))
    )
    (comp (ref "R1")
      (value "2.7k")
      (footprint "eagle-import:.0603-C-NOSILK")
      (fields
        (field (name "MANUFACTURER_PART_NUMBER") "CR0603-FX-2701ELF")
        (field (name "MOUSER_PART_NUMBER") "652-CR0603-FX2701ELF")
        (field (name "MFR") "Samsung")
      )
      (libsource (lib "eagle-import") (part "R0603-2.7K-OHMS"))
    )
    (comp (ref "R2")
      (value "2.7k")
      (footprint "eagle-import:.0603-C-NOSILK")
      (fields
        (field (name "MANUFACTURER_PART_NUMBER") "CR0603-FX-2701ELF")
        (field (name "MOUSER_PART_NUMBER") "652-CR0603-FX2701ELF")
        (field (name "MFR") "Samsung")
      )
      (libsource (lib "eagle-import") (part "R0603-2.7K-OHMS"))
    )
    (comp (ref "R5")
      (value "31.6k")
      (footprint "eagle-import:.0603-C-NOSILK")
      (fields
        (field (name "MANUFACTURER_PART_NUMBER") "CR0603-FX-3162ELF")
        (field (name "MOUSER_PART_NUMBER") "652-CR0603FX-3162ELF")
        (field (name "MFR") "Samsung")
      )
      (libsource (lib "eagle-import") (part "R0603-31.6K-OHMS"))
    )
    (comp (ref "R6")
      (value "3.1k")
      (footprint "eagle-import:.0603-C-NOSILK")
      (fields
        (field (name "MANUFACTURER_PART_NUMBER") "CHP0603-FX-3011ELF")
        (field (name "MOUSER_PART_NUMBER") "652-CHP0603FX3011ELF")
        (field (name "MFR") "Samsung")
      )
      (libsource (lib "eagle-import") (part "R0603-3.1K-OHMS"))
    )
    (comp (ref "R7")
      (value "10k")
      (footprint "eagle-import:.0603-C-NOSILK")
      (fields
        (field (name "MANUFACTURER_PART_NUMBER") "CR0603-FX-1002ELF")
        (field (name "MOUSER_PART_NUMBER") "652-CR0603FX-1002ELF")
        (field (name "RS_PART_NUMBER") "7408805P")
      )
      (libsource (lib "eagle-import") (part "R0603-10K-OHMS"))
    )
    (comp (ref "R9")
      (value "10k")
      (footprint "eagle-import:.0603-C-NOSILK")
      (fields
        (field (name "MANUFACTURER_PART_NUMBER") "CR0603-FX-1002ELF")
        (field (name "MOUSER_PART_NUMBER") "652-CR0603FX-1002ELF")
        (field (name "RS_PART_NUMBER") "7408805P")
      )
      (libsource (lib "eagle-import") (part "R0603-10K-OHMS"))
    )
    (comp (ref "R10")
      (value "NP")
      (footprint "eagle-import:.0603-C-NOSILK")
      (fields
        (field (name "MANUFACTURER_PART_NUMBER") "CRCW06030000Z0EAC")
        (field (name "MOUSER_PART_NUMBER") "71-CRCW06030000Z0EAC")
        (field (name "MFR") "Samsung")
      )
      (libsource (lib "eagle-import") (part "R0603-0-OHMS"))
    )
    (comp (ref "TP1")
      (value "TEST-POINT")
      (footprint "eagle-import:2MM-TEST-POINT")
      (libsource (lib "eagle-import") (part "TEST-POINT"))
    )
    (comp (ref "TP10")
      (value "TEST-POINT")
      (footprint "eagle-import:2MM-TEST-POINT")
      (libsource (lib "eagle-import") (part "TEST-POINT"))
    )
    (comp (ref "TP16")
      (value "TEST-POINT")
      (footprint "eagle-import:2MM-TEST-POINT")
      (libsource (lib "eagle-import") (part "TEST-POINT"))
    )
    (comp (ref "TP17")
      (value "TEST-POINT")
      (footprint "eagle-import:2MM-TEST-POINT")
      (libsource (lib "eagle-import") (part "TEST-POINT"))
    )
    (comp (ref "TP19")
      (value "TEST-POINT")
      (footprint "eagle-import:2MM-TEST-POINT")
      (libsource (lib "eagle-import") (part "TEST-POINT"))
    )
    (comp (ref "TP20")
      (value "TEST-POINT")
      (footprint "eagle-import:2MM-TEST-POINT")
      (libsource (lib "eagle-import") (part "TEST-POINT"))
    )
    (comp (ref "U$1")
      (value "ORESAT-CARD-V1.1-3XRF")
      (footprint "eagle-import:ORESAT-CARD-V1.1-3XRF")
      (libsource (lib "eagle-import") (part "ORESAT-CARD-V1.1-3XRF"))
    )
    (comp (ref "U4")
      (value "TPS259621 - eFuse")
      (footprint "eagle-import:SO-POWERPAD-8")
      (libsource (lib "eagle-import") (part "TPS2596XX"))
    )
    (comp (ref "U5")
      (value "TPS62111RSA")
      (footprint "eagle-import:S-PVQFN-16")
      (fields (field (name "MFR") "TI"))
      (libsource (lib "eagle-import") (part "TPS6211X"))
    )
    (comp (ref "C42")
      (value "8.2pF")
      (footprint "eagle-import:.0603-B-NOSILK")
      (fields
        (field (name "MANUFACTURER_PART_NUMBER") "885012006093")
        (field (name "MOUSER_PART_NUMBER") "710-885012006093")
      )
      (libsource (lib "eagle-import") (part "CAP0603-8.2PF"))
    )
    (comp (ref "C43")
      (value "8.2pF")
      (footprint "eagle-import:.0603-B-NOSILK")
      (fields
        (field (name "MANUFACTURER_PART_NUMBER") "885012006093")
        (field (name "MOUSER_PART_NUMBER") "710-885012006093")
      )
      (libsource (lib "eagle-import") (part "CAP0603-8.2PF"))
    )
    (comp (ref "C44")
      (value "1000pF")
      (footprint "eagle-import:.0603-B-NOSILK")
      (fields
        (field (name "MANUFACTURER_PART_NUMBER") "885012006085")
        (field (name "MOUSER_PART_NUMBER") "710-885012006085")
      )
      (libsource (lib "eagle-import") (part "CAP0603-1000PF"))
    )
    (comp (ref "C45")
      (value "1000pF")
      (footprint "eagle-import:.0603-B-NOSILK")
      (fields
        (field (name "MANUFACTURER_PART_NUMBER") "885012006085")
        (field (name "MOUSER_PART_NUMBER") "710-885012006085")
      )
      (libsource (lib "eagle-import") (part "CAP0603-1000PF"))
    )
    (comp (ref "C46")
      (value "82pF")
      (footprint "eagle-import:.0603-B-NOSILK")
      (fields
        (field (name "MANUFACTURER_PART_NUMBER") "06035A820JAT4A")
        (field (name "MOUSER_PART_NUMBER") "581-06035A820JAT4A")
      )
      (libsource (lib "eagle-import") (part "CAP0603-82PF"))
    )
    (comp (ref "C47")
      (value "82pF")
      (footprint "eagle-import:.0603-B-NOSILK")
      (fields
        (field (name "MANUFACTURER_PART_NUMBER") "06035A820JAT4A")
        (field (name "MOUSER_PART_NUMBER") "581-06035A820JAT4A")
      )
      (libsource (lib "eagle-import") (part "CAP0603-82PF"))
    )
    (comp (ref "C48")
      (value "22pF")
      (footprint "eagle-import:.0603-B-NOSILK")
      (fields
        (field (name "MANUFACTURER_PART_NUMBER") "06035A220JAT4A")
        (field (name "MOUSER_PART_NUMBER") "581-06035A220JAT4A")
      )
      (libsource (lib "eagle-import") (part "CAP0603-22PF"))
    )
    (comp (ref "C49")
      (value "22pF")
      (footprint "eagle-import:.0603-B-NOSILK")
      (fields
        (field (name "MANUFACTURER_PART_NUMBER") "06035A220JAT4A")
        (field (name "MOUSER_PART_NUMBER") "581-06035A220JAT4A")
      )
      (libsource (lib "eagle-import") (part "CAP0603-22PF"))
    )
    (comp (ref "C50")
      (value "0.022uF")
      (footprint "eagle-import:.0603-B-NOSILK")
      (fields
        (field (name "MANUFACTURER_PART_NUMBER") "C0603C223K5RACTU")
        (field (name "MOUSER_PART_NUMBER") "80-C0603C223K5R")
        (field (name "RS_PART_NUMBER") "2644602P")
      )
      (libsource (lib "eagle-import") (part "CAP0603-0.022UF"))
    )
    (comp (ref "C51")
      (value "0.022uF")
      (footprint "eagle-import:.0603-B-NOSILK")
      (fields
        (field (name "MANUFACTURER_PART_NUMBER") "C0603C223K5RACTU")
        (field (name "MOUSER_PART_NUMBER") "80-C0603C223K5R")
        (field (name "RS_PART_NUMBER") "2644602P")
      )
      (libsource (lib "eagle-import") (part "CAP0603-0.022UF"))
    )
    (comp (ref "C52")
      (value "4.7uF")
      (footprint "eagle-import:.0603-B-NOSILK")
      (fields
        (field (name "MANUFACTURER_PART_NUMBER") "C1608X7S1A475K080AC")
        (field (name "MOUSER_PART_NUMBER") "810-C1608X7S1A475KAC")
        (field (name "RS_PART_NUMBER") "9159230P")
      )
      (libsource (lib "eagle-import") (part "CAP0603-4.7UF"))
    )
    (comp (ref "C53")
      (value "0.022uF")
      (footprint "eagle-import:.0603-B-NOSILK")
      (fields
        (field (name "MANUFACTURER_PART_NUMBER") "C0603C223K5RACTU")
        (field (name "MOUSER_PART_NUMBER") "80-C0603C223K5R")
        (field (name "RS_PART_NUMBER") "2644602P")
      )
      (libsource (lib "eagle-import") (part "CAP0603-0.022UF"))
    )
    (comp (ref "C54")
      (value "0.022uF")
      (footprint "eagle-import:.0603-B-NOSILK")
      (fields
        (field (name "MANUFACTURER_PART_NUMBER") "C0603C223K5RACTU")
        (field (name "MOUSER_PART_NUMBER") "80-C0603C223K5R")
        (field (name "RS_PART_NUMBER") "2644602P")
      )
      (libsource (lib "eagle-import") (part "CAP0603-0.022UF"))
    )
    (comp (ref "C55")
      (value "4.7uF")
      (footprint "eagle-import:.0603-B-NOSILK")
      (fields
        (field (name "MANUFACTURER_PART_NUMBER") "C1608X7S1A475K080AC")
        (field (name "MOUSER_PART_NUMBER") "810-C1608X7S1A475KAC")
        (field (name "RS_PART_NUMBER") "9159230P")
      )
      (libsource (lib "eagle-import") (part "CAP0603-4.7UF"))
    )
    (comp (ref "C56")
      (value "10n")
      (footprint "eagle-import:.0603-B-NOSILK")
      (fields
        (field (name "MANUFACTURER_PART_NUMBER") "885382206002")
        (field (name "MOUSER_PART_NUMBER") "710-885382206002")
        (field (name "RS_PART_NUMBER") "1855654P")
      )
      (libsource (lib "eagle-import") (part "CAP0603-0.01UF"))
    )
    (comp (ref "C57")
      (value "1uF")
      (footprint "eagle-import:.0603-B-NOSILK")
      (fields
        (field (name "MANUFACTURER_PART_NUMBER") "0603X105K100CT")
        (field (name "MOUSER_PART_NUMBER") "791-0603X105K100CT")
      )
      (libsource (lib "eagle-import") (part "CAP0603-1UF"))
    )
    (comp (ref "C58")
      (value "8.2pF")
      (footprint "eagle-import:.0603-B-NOSILK")
      (fields
        (field (name "MANUFACTURER_PART_NUMBER") "885012006093")
        (field (name "MOUSER_PART_NUMBER") "710-885012006093")
      )
      (libsource (lib "eagle-import") (part "CAP0603-8.2PF"))
    )
    (comp (ref "C59")
      (value "8.2pF")
      (footprint "eagle-import:.0603-B-NOSILK")
      (fields
        (field (name "MANUFACTURER_PART_NUMBER") "885012006093")
        (field (name "MOUSER_PART_NUMBER") "710-885012006093")
      )
      (libsource (lib "eagle-import") (part "CAP0603-8.2PF"))
    )
    (comp (ref "C60")
      (value "1000pF")
      (footprint "eagle-import:.0603-B-NOSILK")
      (fields
        (field (name "MANUFACTURER_PART_NUMBER") "885012006085")
        (field (name "MOUSER_PART_NUMBER") "710-885012006085")
      )
      (libsource (lib "eagle-import") (part "CAP0603-1000PF"))
    )
    (comp (ref "C61")
      (value "1000pF")
      (footprint "eagle-import:.0603-B-NOSILK")
      (fields
        (field (name "MANUFACTURER_PART_NUMBER") "885012006085")
        (field (name "MOUSER_PART_NUMBER") "710-885012006085")
      )
      (libsource (lib "eagle-import") (part "CAP0603-1000PF"))
    )
    (comp (ref "C62")
      (value "82pF")
      (footprint "eagle-import:.0603-B-NOSILK")
      (fields
        (field (name "MANUFACTURER_PART_NUMBER") "06035A820JAT4A")
        (field (name "MOUSER_PART_NUMBER") "581-06035A820JAT4A")
      )
      (libsource (lib "eagle-import") (part "CAP0603-82PF"))
    )
    (comp (ref "C63")
      (value "82pF")
      (footprint "eagle-import:.0603-B-NOSILK")
      (fields
        (field (name "MANUFACTURER_PART_NUMBER") "06035A820JAT4A")
        (field (name "MOUSER_PART_NUMBER") "581-06035A820JAT4A")
      )
      (libsource (lib "eagle-import") (part "CAP0603-82PF"))
    )
    (comp (ref "C64")
      (value "22pF")
      (footprint "eagle-import:.0603-B-NOSILK")
      (fields
        (field (name "MANUFACTURER_PART_NUMBER") "06035A220JAT4A")
        (field (name "MOUSER_PART_NUMBER") "581-06035A220JAT4A")
      )
      (libsource (lib "eagle-import") (part "CAP0603-22PF"))
    )
    (comp (ref "C65")
      (value "22pF")
      (footprint "eagle-import:.0603-B-NOSILK")
      (fields
        (field (name "MANUFACTURER_PART_NUMBER") "06035A220JAT4A")
        (field (name "MOUSER_PART_NUMBER") "581-06035A220JAT4A")
      )
      (libsource (lib "eagle-import") (part "CAP0603-22PF"))
    )
    (comp (ref "C66")
      (value "0.022uF")
      (footprint "eagle-import:.0603-B-NOSILK")
      (fields
        (field (name "MANUFACTURER_PART_NUMBER") "C0603C223K5RACTU")
        (field (name "MOUSER_PART_NUMBER") "80-C0603C223K5R")
        (field (name "RS_PART_NUMBER") "2644602P")
      )
      (libsource (lib "eagle-import") (part "CAP0603-0.022UF"))
    )
    (comp (ref "C67")
      (value "0.1uf")
      (footprint "eagle-import:.0603-B-NOSILK")
      (fields
        (field (name "MANUFACTURER_PART_NUMBER") "0603ZD104KAT2A")
        (field (name "MOUSER_PART_NUMBER") "581-0603ZD104KAT2A")
      )
      (libsource (lib "eagle-import") (part "CAP0603-0.1UF"))
    )
    (comp (ref "C68")
      (value "4.7uF")
      (footprint "eagle-import:.0603-B-NOSILK")
      (fields
        (field (name "MANUFACTURER_PART_NUMBER") "C1608X7S1A475K080AC")
        (field (name "MOUSER_PART_NUMBER") "810-C1608X7S1A475KAC")
        (field (name "RS_PART_NUMBER") "9159230P")
      )
      (libsource (lib "eagle-import") (part "CAP0603-4.7UF"))
    )
    (comp (ref "C69")
      (value "0.022uF")
      (footprint "eagle-import:.0603-B-NOSILK")
      (fields
        (field (name "MANUFACTURER_PART_NUMBER") "C0603C223K5RACTU")
        (field (name "MOUSER_PART_NUMBER") "80-C0603C223K5R")
        (field (name "RS_PART_NUMBER") "2644602P")
      )
      (libsource (lib "eagle-import") (part "CAP0603-0.022UF"))
    )
    (comp (ref "C70")
      (value "0.1uf")
      (footprint "eagle-import:.0603-B-NOSILK")
      (fields
        (field (name "MANUFACTURER_PART_NUMBER") "0603ZD104KAT2A")
        (field (name "MOUSER_PART_NUMBER") "581-0603ZD104KAT2A")
      )
      (libsource (lib "eagle-import") (part "CAP0603-0.1UF"))
    )
    (comp (ref "C71")
      (value "4.7uF")
      (footprint "eagle-import:.0603-B-NOSILK")
      (fields
        (field (name "MANUFACTURER_PART_NUMBER") "C1608X7S1A475K080AC")
        (field (name "MOUSER_PART_NUMBER") "810-C1608X7S1A475KAC")
        (field (name "RS_PART_NUMBER") "9159230P")
      )
      (libsource (lib "eagle-import") (part "CAP0603-4.7UF"))
    )
    (comp (ref "C72")
      (value "10n")
      (footprint "eagle-import:.0603-B-NOSILK")
      (fields
        (field (name "MANUFACTURER_PART_NUMBER") "885382206002")
        (field (name "MOUSER_PART_NUMBER") "710-885382206002")
        (field (name "RS_PART_NUMBER") "1855654P")
      )
      (libsource (lib "eagle-import") (part "CAP0603-0.01UF"))
    )
    (comp (ref "C73")
      (value "1uF")
      (footprint "eagle-import:.0603-B-NOSILK")
      (fields
        (field (name "MANUFACTURER_PART_NUMBER") "0603X105K100CT")
        (field (name "MOUSER_PART_NUMBER") "791-0603X105K100CT")
      )
      (libsource (lib "eagle-import") (part "CAP0603-1UF"))
    )
    (comp (ref "J8")
      (value "U.FL")
      (footprint "eagle-import:U.FL")
      (libsource (lib "eagle-import") (part "U.FL2PIN"))
    )
    (comp (ref "J9")
      (value "U.FL")
      (footprint "eagle-import:U.FL")
      (libsource (lib "eagle-import") (part "U.FL2PIN"))
    )
    (comp (ref "J10")
      (value "U.FL")
      (footprint "eagle-import:U.FL")
      (libsource (lib "eagle-import") (part "U.FL2PIN"))
    )
    (comp (ref "J11")
      (value "U.FL")
      (footprint "eagle-import:U.FL")
      (libsource (lib "eagle-import") (part "U.FL2PIN"))
    )
    (comp (ref "J13")
      (value "U.FL")
      (footprint "eagle-import:U.FL")
      (libsource (lib "eagle-import") (part "U.FL2PIN"))
    )
    (comp (ref "J14")
      (value "U.FL")
      (footprint "eagle-import:U.FL")
      (libsource (lib "eagle-import") (part "U.FL2PIN"))
    )
    (comp (ref "J15")
      (value "HARWIN-2X8X1.27")
      (footprint "eagle-import:2X8X1.27")
      (libsource (lib "eagle-import") (part "HARWIN-2X8X1.27"))
    )
    (comp (ref "J19")
      (value "HARWIN-2X8X1.27")
      (footprint "eagle-import:2X8X1.27")
      (libsource (lib "eagle-import") (part "HARWIN-2X8X1.27"))
    )
    (comp (ref "L6")
      (value "43n")
      (footprint "eagle-import:.0402-C-NOSILK")
      (libsource (lib "eagle-import") (part "L-US0402-C-NOSILK"))
    )
    (comp (ref "L7")
      (value "43n")
      (footprint "eagle-import:.0402-C-NOSILK")
      (libsource (lib "eagle-import") (part "L-US0402-C-NOSILK"))
    )
    (comp (ref "L8")
      (value "91n")
      (footprint "eagle-import:.0603-C-NOSILK")
      (libsource (lib "eagle-import") (part "L-US0603-C-NOSILK"))
    )
    (comp (ref "L9")
      (value "91n")
      (footprint "eagle-import:.0603-C-NOSILK")
      (libsource (lib "eagle-import") (part "L-US0603-C-NOSILK"))
    )
    (comp (ref "L10")
      (value "43n")
      (footprint "eagle-import:.0402-C-NOSILK")
      (libsource (lib "eagle-import") (part "L-US0402-C-NOSILK"))
    )
    (comp (ref "L11")
      (value "43n")
      (footprint "eagle-import:.0402-C-NOSILK")
      (libsource (lib "eagle-import") (part "L-US0402-C-NOSILK"))
    )
    (comp (ref "L12")
      (value "91n")
      (footprint "eagle-import:.0603-C-NOSILK")
      (libsource (lib "eagle-import") (part "L-US0603-C-NOSILK"))
    )
    (comp (ref "L13")
      (value "91n")
      (footprint "eagle-import:.0603-C-NOSILK")
      (libsource (lib "eagle-import") (part "L-US0603-C-NOSILK"))
    )
    (comp (ref "R28")
      (value "150")
      (footprint "eagle-import:.0603-C-NOSILK")
      (fields
        (field (name "MANUFACTURER_PART_NUMBER") "CR0603-FX-1500ELF")
        (field (name "MOUSER_PART_NUMBER") "652-CR0603FX-1500ELF")
        (field (name "RS_PART_NUMBER") "7408833")
      )
      (libsource (lib "eagle-import") (part "R0603-150-OHMS"))
    )
    (comp (ref "R32")
      (value "0")
      (footprint "eagle-import:.0603-C-NOSILK")
      (fields
        (field (name "MANUFACTURER_PART_NUMBER") "CRCW06030000Z0EAC")
        (field (name "MOUSER_PART_NUMBER") "71-CRCW06030000Z0EAC")
      )
      (libsource (lib "eagle-import") (part "R0603-0-OHMS"))
    )
    (comp (ref "R33")
      (value "0")
      (footprint "eagle-import:.0603-C-NOSILK")
      (fields
        (field (name "MANUFACTURER_PART_NUMBER") "CRCW06030000Z0EAC")
        (field (name "MOUSER_PART_NUMBER") "71-CRCW06030000Z0EAC")
      )
      (libsource (lib "eagle-import") (part "R0603-0-OHMS"))
    )
    (comp (ref "R34")
      (value "150")
      (footprint "eagle-import:.0603-C-NOSILK")
      (fields
        (field (name "MANUFACTURER_PART_NUMBER") "CR0603-FX-1500ELF")
        (field (name "MOUSER_PART_NUMBER") "652-CR0603FX-1500ELF")
        (field (name "RS_PART_NUMBER") "7408833")
      )
      (libsource (lib "eagle-import") (part "R0603-150-OHMS"))
    )
    (comp (ref "R39")
      (value "0")
      (footprint "eagle-import:.0603-C-NOSILK")
      (fields
        (field (name "MANUFACTURER_PART_NUMBER") "CRCW06030000Z0EAC")
        (field (name "MOUSER_PART_NUMBER") "71-CRCW06030000Z0EAC")
      )
      (libsource (lib "eagle-import") (part "R0603-0-OHMS"))
    )
    (comp (ref "R40")
      (value "0")
      (footprint "eagle-import:.0603-C-NOSILK")
      (fields
        (field (name "MANUFACTURER_PART_NUMBER") "CRCW06030000Z0EAC")
        (field (name "MOUSER_PART_NUMBER") "71-CRCW06030000Z0EAC")
      )
      (libsource (lib "eagle-import") (part "R0603-0-OHMS"))
    )
    (comp (ref "U11")
      (value "U-ONSEMI-AX5043")
      (footprint "eagle-import:QFN28-5X5-WITH-CENTER-PAD")
      (libsource (lib "eagle-import") (part "U-ONSEMI-AX5043"))
    )
    (comp (ref "U12")
      (value "LP2985XX-N")
      (footprint "eagle-import:SOT-23")
      (libsource (lib "eagle-import") (part "LP2985XX-N"))
    )
    (comp (ref "U13")
      (value "U-ONSEMI-AX5043")
      (footprint "eagle-import:QFN28-5X5-WITH-CENTER-PAD")
      (libsource (lib "eagle-import") (part "U-ONSEMI-AX5043"))
    )
    (comp (ref "U14")
      (value "LP2985XX-N")
      (footprint "eagle-import:SOT-23")
      (libsource (lib "eagle-import") (part "LP2985XX-N"))
    )
    (comp (ref "X3")
      (value "TAITIEN-TY")
      (footprint "eagle-import:2.5X2.0")
      (libsource (lib "eagle-import") (part "TAITIEN-TY"))
    )
    (comp (ref "X4")
      (value "TAITIEN-TY")
      (footprint "eagle-import:2.5X2.0")
      (libsource (lib "eagle-import") (part "TAITIEN-TY"))
    )
  )
  (nets
    (net (code "1") (name "3.3V") (class "Default")
      (node (ref "C12") (pin "1") (pinfunction "1_1") (pintype "passive"))
      (node (ref "C13") (pin "2") (pinfunction "2_2") (pintype "passive"))
      (node (ref "C17") (pin "2") (pinfunction "2_2") (pintype "passive"))
      (node (ref "C2") (pin "2") (pinfunction "2_2") (pintype "passive"))
      (node (ref "C22") (pin "2") (pinfunction "2_2") (pintype "passive"))
      (node (ref "C3") (pin "2") (pinfunction "2_2") (pintype "passive"))
      (node (ref "C6") (pin "2") (pinfunction "2_2") (pintype "passive"))
      (node (ref "C8") (pin "2") (pinfunction "2_2") (pintype "passive"))
      (node (ref "C9") (pin "2") (pinfunction "2_2") (pintype "passive"))
      (node (ref "D7") (pin "2") (pinfunction "A_2") (pintype "passive"))
      (node (ref "J7") (pin "1") (pinfunction "VTREF_1") (pintype "passive"))
      (node (ref "L2") (pin "2") (pinfunction "2_2") (pintype "passive"))
      (node (ref "Q1") (pin "4") (pinfunction "S_4") (pintype "passive"))
      (node (ref "R12") (pin "2") (pinfunction "2_2") (pintype "passive"))
      (node (ref "R13") (pin "1") (pinfunction "1_1") (pintype "passive"))
      (node (ref "R14") (pin "10") (pinfunction "55_10") (pintype "passive"))
      (node (ref "R14") (pin "5") (pinfunction "55_5") (pintype "passive"))
      (node (ref "R15") (pin "10") (pinfunction "55_10") (pintype "passive"))
      (node (ref "R15") (pin "5") (pinfunction "55_5") (pintype "passive"))
      (node (ref "R16") (pin "2") (pinfunction "2_2") (pintype "passive"))
      (node (ref "R2") (pin "2") (pinfunction "2_2") (pintype "passive"))
      (node (ref "R27") (pin "2") (pinfunction "2_2") (pintype "passive"))
      (node (ref "R32") (pin "1") (pinfunction "1_1") (pintype "passive"))
      (node (ref "R33") (pin "2") (pinfunction "2_2") (pintype "passive"))
      (node (ref "R39") (pin "1") (pinfunction "1_1") (pintype "passive"))
      (node (ref "R40") (pin "2") (pinfunction "2_2") (pintype "passive"))
      (node (ref "TP17") (pin "1") (pinfunction "1_1") (pintype "passive"))
      (node (ref "U2") (pin "3") (pinfunction "VCC_3") (pintype "power_in"))
      (node (ref "U3") (pin "3") (pinfunction "VCC_3") (pintype "power_in"))
      (node (ref "U5") (pin "10") (pinfunction "FB_10") (pintype "input"))
      (node (ref "U7") (pin "1") (pinfunction "VBAT_1") (pintype "power_in"))
      (node (ref "U7") (pin "13") (pinfunction "VDDA_13") (pintype "power_in"))
      (node (ref "U7") (pin "19") (pinfunction "VDD_19") (pintype "power_in"))
      (node (ref "U7") (pin "32") (pinfunction "VDD_32") (pintype "power_in"))
      (node (ref "U7") (pin "48") (pinfunction "VDD_48") (pintype "power_in"))
      (node (ref "U7") (pin "64") (pinfunction "VDD_64") (pintype "power_in"))
    )
    (net (code "2") (name "AUX-1") (class "Default")
      (node (ref "J1") (pin "1") (pinfunction "1_1") (pintype "passive"))
      (node (ref "J1") (pin "2") (pinfunction "2_2") (pintype "passive"))
      (node (ref "JP9") (pin "1") (pinfunction "1_1") (pintype "passive"))
    )
    (net (code "3") (name "AUX-2") (class "Default")
      (node (ref "J1") (pin "3") (pinfunction "3_3") (pintype "passive"))
      (node (ref "J1") (pin "4") (pinfunction "4_4") (pintype "passive"))
      (node (ref "JP9") (pin "2") (pinfunction "2_2") (pintype "passive"))
    )
    (net (code "4") (name "AUX-3") (class "Default")
      (node (ref "J1") (pin "5") (pinfunction "5_5") (pintype "passive"))
      (node (ref "J1") (pin "6") (pinfunction "6_6") (pintype "passive"))
      (node (ref "JP9") (pin "3") (pinfunction "3_3") (pintype "passive"))
    )
    (net (code "5") (name "AUX-4") (class "Default")
      (node (ref "J1") (pin "7") (pinfunction "7_7") (pintype "passive"))
      (node (ref "J1") (pin "8") (pinfunction "8_8") (pintype "passive"))
      (node (ref "JP9") (pin "4") (pinfunction "4_4") (pintype "passive"))
    )
    (net (code "6") (name "AUX-5") (class "Default")
      (node (ref "J1") (pin "10") (pinfunction "10_10") (pintype "passive"))
      (node (ref "J1") (pin "9") (pinfunction "9_9") (pintype "passive"))
      (node (ref "JP9") (pin "5") (pinfunction "5_5") (pintype "passive"))
    )
    (net (code "7") (name "AUX-6") (class "Default")
      (node (ref "J1") (pin "11") (pinfunction "11_11") (pintype "passive"))
      (node (ref "J1") (pin "12") (pinfunction "12_12") (pintype "passive"))
      (node (ref "JP9") (pin "6") (pinfunction "6_6") (pintype "passive"))
    )
    (net (code "8") (name "AUX-7") (class "Default")
      (node (ref "J1") (pin "13") (pinfunction "13_13") (pintype "passive"))
      (node (ref "J1") (pin "14") (pinfunction "14_14") (pintype "passive"))
      (node (ref "JP9") (pin "7") (pinfunction "7_7") (pintype "passive"))
    )
    (net (code "9") (name "AUX-8") (class "Default")
      (node (ref "J1") (pin "15") (pinfunction "15_15") (pintype "passive"))
      (node (ref "J1") (pin "16") (pinfunction "16_16") (pintype "passive"))
      (node (ref "JP9") (pin "8") (pinfunction "8_8") (pintype "passive"))
    )
    (net (code "10") (name "AUX-9") (class "Default")
      (node (ref "J1") (pin "17") (pinfunction "17_17") (pintype "passive"))
      (node (ref "J1") (pin "18") (pinfunction "18_18") (pintype "passive"))
      (node (ref "JP9") (pin "9") (pinfunction "9_9") (pintype "passive"))
    )
    (net (code "11") (name "AUX_~{SHUTDOWN}") (class "Default")
      (node (ref "J1") (pin "19") (pinfunction "19_19") (pintype "passive"))
      (node (ref "J1") (pin "20") (pinfunction "20_20") (pintype "passive"))
      (node (ref "JP9") (pin "10") (pinfunction "10_10") (pintype "passive"))
    )
    (net (code "12") (name "CAN1_H") (class "Default")
      (node (ref "J6") (pin "33") (pinfunction "33_33") (pintype "passive"))
      (node (ref "J6") (pin "34") (pinfunction "34_34") (pintype "passive"))
      (node (ref "JP10") (pin "5") (pinfunction "5_5") (pintype "passive"))
      (node (ref "JP10") (pin "6") (pinfunction "6_6") (pintype "passive"))
      (node (ref "U2") (pin "7") (pinfunction "CANH_7") (pintype "bidirectional"))
    )
    (net (code "13") (name "CAN1_L") (class "Default")
      (node (ref "J6") (pin "35") (pinfunction "35_35") (pintype "passive"))
      (node (ref "J6") (pin "36") (pinfunction "36_36") (pintype "passive"))
      (node (ref "JP10") (pin "7") (pinfunction "7_7") (pintype "passive"))
      (node (ref "JP10") (pin "8") (pinfunction "8_8") (pintype "passive"))
      (node (ref "U2") (pin "6") (pinfunction "CANL_6") (pintype "bidirectional"))
    )
    (net (code "14") (name "CAN1_RX") (class "Default")
      (node (ref "U2") (pin "4") (pinfunction "RXD_4") (pintype "output"))
      (node (ref "U7") (pin "44") (pinfunction "PA11_44") (pintype "bidirectional"))
    )
    (net (code "15") (name "CAN1_SHDN") (class "Default")
      (node (ref "U2") (pin "5") (pinfunction "SHDN_5") (pintype "input"))
      (node (ref "U7") (pin "43") (pinfunction "PA10_43") (pintype "bidirectional"))
    )
    (net (code "16") (name "CAN1_SILENT") (class "Default")
      (node (ref "U2") (pin "8") (pinfunction "S_8") (pintype "input"))
      (node (ref "U7") (pin "42") (pinfunction "PA9_42") (pintype "bidirectional"))
    )
    (net (code "17") (name "CAN1_TX") (class "Default")
      (node (ref "U2") (pin "1") (pinfunction "TXD_1") (pintype "input"))
      (node (ref "U7") (pin "45") (pinfunction "PA12_45") (pintype "bidirectional"))
    )
    (net (code "18") (name "CAN2_H") (class "Default")
      (node (ref "J6") (pin "17") (pinfunction "17_17") (pintype "passive"))
      (node (ref "J6") (pin "18") (pinfunction "18_18") (pintype "passive"))
      (node (ref "JP1") (pin "7") (pinfunction "7_7") (pintype "passive"))
      (node (ref "JP1") (pin "8") (pinfunction "8_8") (pintype "passive"))
      (node (ref "U3") (pin "7") (pinfunction "CANH_7") (pintype "bidirectional"))
    )
    (net (code "19") (name "CAN2_L") (class "Default")
      (node (ref "J6") (pin "19") (pinfunction "19_19") (pintype "passive"))
      (node (ref "J6") (pin "20") (pinfunction "20_20") (pintype "passive"))
      (node (ref "JP1") (pin "10") (pinfunction "10_10") (pintype "passive"))
      (node (ref "JP1") (pin "9") (pinfunction "9_9") (pintype "passive"))
      (node (ref "U3") (pin "6") (pinfunction "CANL_6") (pintype "bidirectional"))
    )
    (net (code "20") (name "CAN2_RX") (class "Default")
      (node (ref "U3") (pin "4") (pinfunction "RXD_4") (pintype "output"))
      (node (ref "U7") (pin "57") (pinfunction "PB5_57") (pintype "bidirectional"))
    )
    (net (code "21") (name "CAN2_SHDN") (class "Default")
      (node (ref "U3") (pin "5") (pinfunction "SHDN_5") (pintype "input"))
      (node (ref "U7") (pin "56") (pinfunction "PB4_56") (pintype "bidirectional"))
    )
    (net (code "22") (name "CAN2_SILENT") (class "Default")
      (node (ref "U3") (pin "8") (pinfunction "S_8") (pintype "input"))
      (node (ref "U7") (pin "59") (pinfunction "PB7_59") (pintype "bidirectional"))
    )
    (net (code "23") (name "CAN2_TX") (class "Default")
      (node (ref "U3") (pin "1") (pinfunction "TXD_1") (pintype "input"))
      (node (ref "U7") (pin "58") (pinfunction "PB6_58") (pintype "bidirectional"))
    )
    (net (code "24") (name "CB_IOUT") (class "Default")
      (node (ref "R20") (pin "1") (pinfunction "1_1") (pintype "passive"))
      (node (ref "R6") (pin "2") (pinfunction "2_2") (pintype "passive"))
      (node (ref "TP10") (pin "1") (pinfunction "1_1") (pintype "passive"))
      (node (ref "U4") (pin "7") (pinfunction "ILIM_7") (pintype "bidirectional"))
    )
    (net (code "25") (name "CB_IOUT_IN") (class "Default")
      (node (ref "R20") (pin "2") (pinfunction "2_2") (pintype "passive"))
      (node (ref "U7") (pin "26") (pinfunction "PB0_26") (pintype "bidirectional"))
    )
    (net (code "26") (name "GND") (class "Default")
      (node (ref "C1") (pin "2") (pinfunction "2_2") (pintype "passive"))
      (node (ref "C10") (pin "2") (pinfunction "2_2") (pintype "passive"))
      (node (ref "C11") (pin "2") (pinfunction "2_2") (pintype "passive"))
      (node (ref "C12") (pin "2") (pinfunction "2_2") (pintype "passive"))
      (node (ref "C13") (pin "1") (pinfunction "1_1") (pintype "passive"))
      (node (ref "C14") (pin "2") (pinfunction "2_2") (pintype "passive"))
      (node (ref "C15") (pin "2") (pinfunction "2_2") (pintype "passive"))
      (node (ref "C16") (pin "2") (pinfunction "2_2") (pintype "passive"))
      (node (ref "C17") (pin "1") (pinfunction "1_1") (pintype "passive"))
      (node (ref "C18") (pin "2") (pinfunction "2_2") (pintype "passive"))
      (node (ref "C19") (pin "2") (pinfunction "2_2") (pintype "passive"))
      (node (ref "C2") (pin "1") (pinfunction "1_1") (pintype "passive"))
      (node (ref "C21") (pin "2") (pinfunction "2_2") (pintype "passive"))
      (node (ref "C22") (pin "1") (pinfunction "1_1") (pintype "passive"))
      (node (ref "C23") (pin "2") (pinfunction "2_2") (pintype "passive"))
      (node (ref "C24") (pin "2") (pinfunction "2_2") (pintype "passive"))
      (node (ref "C25") (pin "2") (pinfunction "2_2") (pintype "passive"))
      (node (ref "C26") (pin "2") (pinfunction "2_2") (pintype "passive"))
      (node (ref "C3") (pin "1") (pinfunction "1_1") (pintype "passive"))
      (node (ref "C4") (pin "2") (pinfunction "2_2") (pintype "passive"))
      (node (ref "C43") (pin "1") (pinfunction "1_1") (pintype "passive"))
      (node (ref "C44") (pin "2") (pinfunction "2_2") (pintype "passive"))
      (node (ref "C46") (pin "2") (pinfunction "2_2") (pintype "passive"))
      (node (ref "C47") (pin "1") (pinfunction "1_1") (pintype "passive"))
      (node (ref "C5") (pin "2") (pinfunction "2_2") (pintype "passive"))
      (node (ref "C50") (pin "2") (pinfunction "2_2") (pintype "passive"))
      (node (ref "C51") (pin "2") (pinfunction "2_2") (pintype "passive"))
      (node (ref "C52") (pin "2") (pinfunction "2_2") (pintype "passive"))
      (node (ref "C53") (pin "2") (pinfunction "2_2") (pintype "passive"))
      (node (ref "C54") (pin "2") (pinfunction "2_2") (pintype "passive"))
      (node (ref "C55") (pin "2") (pinfunction "2_2") (pintype "passive"))
      (node (ref "C56") (pin "2") (pinfunction "2_2") (pintype "passive"))
      (node (ref "C57") (pin "2") (pinfunction "2_2") (pintype "passive"))
      (node (ref "C59") (pin "1") (pinfunction "1_1") (pintype "passive"))
      (node (ref "C6") (pin "1") (pinfunction "1_1") (pintype "passive"))
      (node (ref "C60") (pin "2") (pinfunction "2_2") (pintype "passive"))
      (node (ref "C62") (pin "2") (pinfunction "2_2") (pintype "passive"))
      (node (ref "C63") (pin "1") (pinfunction "1_1") (pintype "passive"))
      (node (ref "C66") (pin "2") (pinfunction "2_2") (pintype "passive"))
      (node (ref "C67") (pin "2") (pinfunction "2_2") (pintype "passive"))
      (node (ref "C68") (pin "2") (pinfunction "2_2") (pintype "passive"))
      (node (ref "C69") (pin "2") (pinfunction "2_2") (pintype "passive"))
      (node (ref "C7") (pin "2") (pinfunction "2_2") (pintype "passive"))
      (node (ref "C70") (pin "2") (pinfunction "2_2") (pintype "passive"))
      (node (ref "C71") (pin "2") (pinfunction "2_2") (pintype "passive"))
      (node (ref "C72") (pin "2") (pinfunction "2_2") (pintype "passive"))
      (node (ref "C73") (pin "2") (pinfunction "2_2") (pintype "passive"))
      (node (ref "C8") (pin "1") (pinfunction "1_1") (pintype "passive"))
      (node (ref "C9") (pin "1") (pinfunction "1_1") (pintype "passive"))
      (node (ref "CM1") (pin "P$1") (pinfunction "SHIELD3_P$1") (pintype "passive"))
      (node (ref "CM1") (pin "P$2") (pinfunction "SHIELD2_P$2") (pintype "passive"))
      (node (ref "CM1") (pin "P$3") (pinfunction "SHIELD1_P$3") (pintype "passive"))
      (node (ref "CM1") (pin "P$4") (pinfunction "SHIELD_P$4") (pintype "passive"))
      (node (ref "CM2") (pin "P$1") (pinfunction "SHIELD3_P$1") (pintype "passive"))
      (node (ref "CM2") (pin "P$2") (pinfunction "SHIELD2_P$2") (pintype "passive"))
      (node (ref "CM2") (pin "P$3") (pinfunction "SHIELD1_P$3") (pintype "passive"))
      (node (ref "CM2") (pin "P$4") (pinfunction "SHIELD_P$4") (pintype "passive"))
      (node (ref "CM3") (pin "P$1") (pinfunction "SHIELD3_P$1") (pintype "passive"))
      (node (ref "CM3") (pin "P$2") (pinfunction "SHIELD2_P$2") (pintype "passive"))
      (node (ref "CM3") (pin "P$3") (pinfunction "SHIELD1_P$3") (pintype "passive"))
      (node (ref "CM3") (pin "P$4") (pinfunction "SHIELD_P$4") (pintype "passive"))
      (node (ref "D1") (pin "C") (pinfunction "C_C") (pintype "passive"))
      (node (ref "D2") (pin "C") (pinfunction "C_C") (pintype "passive"))
      (node (ref "D3") (pin "C") (pinfunction "C_C") (pintype "passive"))
      (node (ref "D5") (pin "C") (pinfunction "C_C") (pintype "passive"))
      (node (ref "J10") (pin "1") (pinfunction "GND_1") (pintype "bidirectional"))
      (node (ref "J10") (pin "2") (pinfunction "GND_2") (pintype "bidirectional"))
      (node (ref "J11") (pin "1") (pinfunction "GND_1") (pintype "bidirectional"))
      (node (ref "J11") (pin "2") (pinfunction "GND_2") (pintype "bidirectional"))
      (node (ref "J13") (pin "1") (pinfunction "GND_1") (pintype "bidirectional"))
      (node (ref "J13") (pin "2") (pinfunction "GND_2") (pintype "bidirectional"))
      (node (ref "J14") (pin "1") (pinfunction "GND_1") (pintype "bidirectional"))
      (node (ref "J14") (pin "2") (pinfunction "GND_2") (pintype "bidirectional"))
      (node (ref "J15") (pin "13") (pinfunction "13_13") (pintype "passive"))
      (node (ref "J15") (pin "14") (pinfunction "14_14") (pintype "passive"))
      (node (ref "J15") (pin "15") (pinfunction "15_15") (pintype "passive"))
      (node (ref "J15") (pin "16") (pinfunction "16_16") (pintype "passive"))
      (node (ref "J19") (pin "13") (pinfunction "13_13") (pintype "passive"))
      (node (ref "J19") (pin "14") (pinfunction "14_14") (pintype "passive"))
      (node (ref "J19") (pin "15") (pinfunction "15_15") (pintype "passive"))
      (node (ref "J19") (pin "16") (pinfunction "16_16") (pintype "passive"))
      (node (ref "J2") (pin "1") (pinfunction "GND_1") (pintype "bidirectional"))
      (node (ref "J2") (pin "2") (pinfunction "GND_2") (pintype "bidirectional"))
      (node (ref "J3") (pin "1") (pinfunction "GND_1") (pintype "bidirectional"))
      (node (ref "J3") (pin "2") (pinfunction "GND_2") (pintype "bidirectional"))
      (node (ref "J4") (pin "1") (pinfunction "GND_1") (pintype "bidirectional"))
      (node (ref "J4") (pin "2") (pinfunction "GND_2") (pintype "bidirectional"))
      (node (ref "J6") (pin "27") (pinfunction "27_27") (pintype "passive"))
      (node (ref "J6") (pin "28") (pinfunction "28_28") (pintype "passive"))
      (node (ref "J6") (pin "29") (pinfunction "29_29") (pintype "passive"))
      (node (ref "J6") (pin "30") (pinfunction "30_30") (pintype "passive"))
      (node (ref "J6") (pin "31") (pinfunction "31_31") (pintype "passive"))
      (node (ref "J6") (pin "32") (pinfunction "32_32") (pintype "passive"))
      (node (ref "J6") (pin "37") (pinfunction "37_37") (pintype "passive"))
      (node (ref "J6") (pin "38") (pinfunction "38_38") (pintype "passive"))
      (node (ref "J7") (pin "3") (pinfunction "GND_3") (pintype "passive"))
      (node (ref "J7") (pin "5") (pinfunction "GND_5") (pintype "passive"))
      (node (ref "J7") (pin "9") (pinfunction "GNDDET_9") (pintype "passive"))
      (node (ref "J8") (pin "1") (pinfunction "GND_1") (pintype "bidirectional"))
      (node (ref "J8") (pin "2") (pinfunction "GND_2") (pintype "bidirectional"))
      (node (ref "J9") (pin "1") (pinfunction "GND_1") (pintype "bidirectional"))
      (node (ref "J9") (pin "2") (pinfunction "GND_2") (pintype "bidirectional"))
      (node (ref "L11") (pin "1") (pinfunction "1_1") (pintype "passive"))
      (node (ref "L12") (pin "2") (pinfunction "2_2") (pintype "passive"))
      (node (ref "L13") (pin "1") (pinfunction "1_1") (pintype "passive"))
      (node (ref "L7") (pin "1") (pinfunction "1_1") (pintype "passive"))
      (node (ref "L8") (pin "2") (pinfunction "2_2") (pintype "passive"))
      (node (ref "L9") (pin "1") (pinfunction "1_1") (pintype "passive"))
      (node (ref "R10") (pin "1") (pinfunction "1_1") (pintype "passive"))
      (node (ref "R17") (pin "1") (pinfunction "1_1") (pintype "passive"))
      (node (ref "R36") (pin "1") (pinfunction "1_1") (pintype "passive"))
      (node (ref "R6") (pin "1") (pinfunction "1_1") (pintype "passive"))
      (node (ref "R9") (pin "1") (pinfunction "1_1") (pintype "passive"))
      (node (ref "TP11") (pin "1") (pinfunction "1_1") (pintype "passive"))
      (node (ref "U$2") (pin "P$6") (pinfunction "GND_P$6") (pintype "passive"))
      (node (ref "U1") (pin "4") (pinfunction "GND_4") (pintype "power_in"))
      (node (ref "U11") (pin "2") (pinfunction "GND1_2") (pintype "power_in"))
      (node (ref "U11") (pin "25") (pinfunction "GPADC1_25") (pintype "input"))
      (node (ref "U11") (pin "26") (pinfunction "GPADC2_26") (pintype "input"))
      (node (ref "U11") (pin "6") (pinfunction "GND2_6") (pintype "power_in"))
      (node (ref "U11") (pin "PAD") (pinfunction "PGND_PAD") (pintype "power_in"))
      (node (ref "U12") (pin "2") (pinfunction "GND_2") (pintype "power_in"))
      (node (ref "U13") (pin "2") (pinfunction "GND1_2") (pintype "power_in"))
      (node (ref "U13") (pin "25") (pinfunction "GPADC1_25") (pintype "input"))
      (node (ref "U13") (pin "26") (pinfunction "GPADC2_26") (pintype "input"))
      (node (ref "U13") (pin "6") (pinfunction "GND2_6") (pintype "power_in"))
      (node (ref "U13") (pin "PAD") (pinfunction "PGND_PAD") (pintype "power_in"))
      (node (ref "U14") (pin "2") (pinfunction "GND_2") (pintype "power_in"))
      (node (ref "U2") (pin "2") (pinfunction "GND_2") (pintype "power_in"))
      (node (ref "U3") (pin "2") (pinfunction "GND_2") (pintype "power_in"))
      (node (ref "U4") (pin "1") (pinfunction "GND_1") (pintype "bidirectional"))
      (node (ref "U4") (pin "THERMAL") (pinfunction "GND_THERMAL") (pintype "bidirectional"))
      (node (ref "U5") (pin "1") (pinfunction "GND_1") (pintype "power_in"))
      (node (ref "U5") (pin "11") (pinfunction "GND_11") (pintype "power_in"))
      (node (ref "U5") (pin "12") (pinfunction "GND_12") (pintype "power_in"))
      (node (ref "U5") (pin "16") (pinfunction "GND_16") (pintype "power_in"))
      (node (ref "U5") (pin "6") (pinfunction "LBO_6") (pintype "open_collector"))
      (node (ref "U5") (pin "7") (pinfunction "LBI_7") (pintype "input"))
      (node (ref "U5") (pin "9") (pinfunction "GND_9") (pintype "power_in"))
      (node (ref "U5") (pin "PAD") (pinfunction "GND_PAD") (pintype "power_in"))
      (node (ref "U6") (pin "2") (pinfunction "GND_2") (pintype "power_in"))
      (node (ref "U6") (pin "5") (pinfunction "SET1_5") (pintype "input"))
      (node (ref "U6") (pin "6") (pinfunction "SET2_6") (pintype "input"))
      (node (ref "U7") (pin "12") (pinfunction "VSSA_12") (pintype "power_in"))
      (node (ref "U7") (pin "18") (pinfunction "VSS_18") (pintype "power_in"))
      (node (ref "U7") (pin "31") (pinfunction "VSS_31") (pintype "power_in"))
      (node (ref "U7") (pin "47") (pinfunction "VSS_47") (pintype "power_in"))
      (node (ref "U7") (pin "63") (pinfunction "VSS_63") (pintype "power_in"))
      (node (ref "U9") (pin "A6") (pinfunction "VSSIO_A6") (pintype "power_in"))
      (node (ref "U9") (pin "C4") (pinfunction "VSSQ_C4") (pintype "power_in"))
      (node (ref "U9") (pin "D4") (pinfunction "VSSIO_D4") (pintype "power_in"))
      (node (ref "U9") (pin "E7") (pinfunction "VSSIO_E7") (pintype "power_in"))
      (node (ref "U9") (pin "G5") (pinfunction "VSSIO_G5") (pintype "power_in"))
      (node (ref "U9") (pin "H10") (pinfunction "VSSIO_H10") (pintype "power_in"))
      (node (ref "U9") (pin "J5") (pinfunction "VSSIO_J5") (pintype "power_in"))
      (node (ref "U9") (pin "K8") (pinfunction "VSSIO_K8") (pintype "power_in"))
      (node (ref "U9") (pin "N1") (pinfunction "VSSQ_N1") (pintype "power_in"))
      (node (ref "U9") (pin "N2") (pinfunction "VSSQ_N2") (pintype "power_in"))
      (node (ref "U9") (pin "N5") (pinfunction "VSSQ_N5") (pintype "power_in"))
      (node (ref "U9") (pin "P4") (pinfunction "VSSQ_P4") (pintype "power_in"))
      (node (ref "U9") (pin "P6") (pinfunction "VSSQ_P6") (pintype "power_in"))
      (node (ref "X1") (pin "2") (pinfunction "SHIELD_2") (pintype "power_in"))
      (node (ref "X1") (pin "4") (pinfunction "SHIELD_4") (pintype "power_in"))
      (node (ref "X3") (pin "2") (pinfunction "GND_2") (pintype "power_in"))
      (node (ref "X4") (pin "2") (pinfunction "GND_2") (pintype "power_in"))
    )
    (net (code "27") (name "MMC_PWR") (class "Default")
      (node (ref "Q1") (pin "3") (pinfunction "G_3") (pintype "passive"))
      (node (ref "R15") (pin "6") (pinfunction "66_6") (pintype "passive"))
      (node (ref "U7") (pin "2") (pinfunction "PC13_2") (pintype "bidirectional"))
    )
    (net (code "28") (name "MMC_VDD") (class "Default")
      (node (ref "C23") (pin "1") (pinfunction "1_1") (pintype "passive"))
      (node (ref "C24") (pin "1") (pinfunction "1_1") (pintype "passive"))
      (node (ref "C25") (pin "1") (pinfunction "1_1") (pintype "passive"))
      (node (ref "C26") (pin "1") (pinfunction "1_1") (pintype "passive"))
      (node (ref "Q1") (pin "1") (pinfunction "D_1") (pintype "passive"))
      (node (ref "Q1") (pin "2") (pinfunction "D_2") (pintype "passive"))
      (node (ref "Q1") (pin "5") (pinfunction "D_5") (pintype "passive"))
      (node (ref "Q1") (pin "6") (pinfunction "D_6") (pintype "passive"))
      (node (ref "U9") (pin "C6") (pinfunction "VDDQ_C6") (pintype "power_in"))
      (node (ref "U9") (pin "E6") (pinfunction "VDDIO_E6") (pintype "power_in"))
      (node (ref "U9") (pin "F5") (pinfunction "VDDIO_F5") (pintype "power_in"))
      (node (ref "U9") (pin "J10") (pinfunction "VDDIO_J10") (pintype "power_in"))
      (node (ref "U9") (pin "K9") (pinfunction "VDDIO_K9") (pintype "power_in"))
      (node (ref "U9") (pin "M4") (pinfunction "VDDQ_M4") (pintype "power_in"))
      (node (ref "U9") (pin "N4") (pinfunction "VDDQ_N4") (pintype "power_in"))
      (node (ref "U9") (pin "P3") (pinfunction "VDDQ_P3") (pintype "power_in"))
      (node (ref "U9") (pin "P5") (pinfunction "VDDQ_P5") (pintype "power_in"))
    )
    (net (code "29") (name "NRST") (class "Default")
      (node (ref "J7") (pin "10") (pinfunction "~{RESET}_10") (pintype "passive"))
      (node (ref "TP2") (pin "1") (pinfunction "1_1") (pintype "passive"))
      (node (ref "U7") (pin "7") (pinfunction "NRST_7") (pintype "bidirectional"))
    )
    (net (code "30") (name "Net-(C42-Pad1)") (class "Default")
      (node (ref "C42") (pin "1") (pinfunction "1_1") (pintype "passive"))
      (node (ref "C48") (pin "2") (pinfunction "2_2") (pintype "passive"))
      (node (ref "L6") (pin "1") (pinfunction "1_1") (pintype "passive"))
    )
    (net (code "31") (name "Net-(C58-Pad1)") (class "Default")
      (node (ref "C58") (pin "1") (pinfunction "1_1") (pintype "passive"))
      (node (ref "C64") (pin "2") (pinfunction "2_2") (pintype "passive"))
      (node (ref "L10") (pin "1") (pinfunction "1_1") (pintype "passive"))
    )
    (net (code "32") (name "Net-(CM1-CENTER)") (class "Default")
      (node (ref "CM1") (pin "RF") (pinfunction "CENTER_RF") (pintype "passive"))
      (node (ref "J2") (pin "FEED") (pinfunction "SIGNAL_FEED") (pintype "bidirectional"))
    )
    (net (code "33") (name "Net-(CM2-CENTER)") (class "Default")
      (node (ref "CM2") (pin "RF") (pinfunction "CENTER_RF") (pintype "passive"))
      (node (ref "J3") (pin "FEED") (pinfunction "SIGNAL_FEED") (pintype "bidirectional"))
    )
    (net (code "34") (name "Net-(CM3-CENTER)") (class "Default")
      (node (ref "CM3") (pin "RF") (pinfunction "CENTER_RF") (pintype "passive"))
      (node (ref "J4") (pin "FEED") (pinfunction "SIGNAL_FEED") (pintype "bidirectional"))
    )
    (net (code "35") (name "Net-(D1-PadA)") (class "Default")
      (node (ref "D1") (pin "A") (pinfunction "A_A") (pintype "passive"))
      (node (ref "R1") (pin "1") (pinfunction "1_1") (pintype "passive"))
    )
    (net (code "36") (name "Net-(D2-PadA)") (class "Default")
      (node (ref "D2") (pin "A") (pinfunction "A_A") (pintype "passive"))
      (node (ref "R2") (pin "1") (pinfunction "1_1") (pintype "passive"))
    )
    (net (code "37") (name "Net-(D3-PadA)") (class "Default")
      (node (ref "D3") (pin "A") (pinfunction "A_A") (pintype "passive"))
      (node (ref "R3") (pin "1") (pinfunction "1_1") (pintype "passive"))
    )
    (net (code "38") (name "Net-(D4-PadA)") (class "Default")
      (node (ref "D4") (pin "A") (pinfunction "A_A") (pintype "passive"))
      (node (ref "R27") (pin "1") (pinfunction "1_1") (pintype "passive"))
    )
    (net (code "39") (name "Net-(D5-PadA)") (class "Default")
      (node (ref "D5") (pin "A") (pinfunction "A_A") (pintype "passive"))
      (node (ref "R4") (pin "1") (pinfunction "1_1") (pintype "passive"))
    )
    (net (code "40") (name "Net-(D7-C)") (class "Default")
      (node (ref "D7") (pin "1") (pinfunction "C_1") (pintype "passive"))
      (node (ref "R19") (pin "2") (pinfunction "2_2") (pintype "passive"))
    )
    (net (code "41") (name "Net-(J9-SIGNAL)") (class "Default")
      (node (ref "C49") (pin "1") (pinfunction "1_1") (pintype "passive"))
      (node (ref "J9") (pin "FEED") (pinfunction "SIGNAL_FEED") (pintype "bidirectional"))
    )
    (net (code "42") (name "Net-(J10-SIGNAL)") (class "Default")
      (node (ref "C48") (pin "1") (pinfunction "1_1") (pintype "passive"))
      (node (ref "J10") (pin "FEED") (pinfunction "SIGNAL_FEED") (pintype "bidirectional"))
    )
    (net (code "43") (name "Net-(J11-SIGNAL)") (class "Default")
      (node (ref "C64") (pin "1") (pinfunction "1_1") (pintype "passive"))
      (node (ref "J11") (pin "FEED") (pinfunction "SIGNAL_FEED") (pintype "bidirectional"))
    )
    (net (code "44") (name "Net-(J13-SIGNAL)") (class "Default")
      (node (ref "C65") (pin "1") (pinfunction "1_1") (pintype "passive"))
      (node (ref "J13") (pin "FEED") (pinfunction "SIGNAL_FEED") (pintype "bidirectional"))
    )
    (net (code "45") (name "Net-(J14-SIGNAL)") (class "Default")
      (node (ref "J14") (pin "FEED") (pinfunction "SIGNAL_FEED") (pintype "bidirectional"))
      (node (ref "U13") (pin "13") (pinfunction "SYSCLK_13") (pintype "bidirectional"))
    )
    (net (code "46") (name "Net-(L2-Pad1)") (class "Default")
      (node (ref "L2") (pin "1") (pinfunction "1_1") (pintype "passive"))
      (node (ref "U5") (pin "14") (pinfunction "SW_14") (pintype "output"))
      (node (ref "U5") (pin "15") (pinfunction "SW_15") (pintype "output"))
    )
    (net (code "47") (name "Net-(U$2-VCC)") (class "Default")
      (node (ref "JP8") (pin "2") (pinfunction "2_2") (pintype "passive"))
      (node (ref "U$2") (pin "P$4") (pinfunction "VCC_P$4") (pintype "passive"))
    )
    (net (code "48") (name "Net-(U1-IN)") (class "Default")
      (node (ref "C5") (pin "1") (pinfunction "1_1") (pintype "passive"))
      (node (ref "R12") (pin "1") (pinfunction "1_1") (pintype "passive"))
      (node (ref "U1") (pin "1") (pinfunction "IN_2_1") (pintype "power_in"))
      (node (ref "U1") (pin "2") (pinfunction "IN_2") (pintype "power_in"))
    )
    (net (code "49") (name "Net-(U4-EN{slash}UVLO)") (class "Default")
      (node (ref "R5") (pin "1") (pinfunction "1_1") (pintype "passive"))
      (node (ref "R9") (pin "2") (pinfunction "2_2") (pintype "passive"))
      (node (ref "U4") (pin "3") (pinfunction "EN/UVLO_3") (pintype "bidirectional"))
    )
    (net (code "50") (name "Net-(U4-~{FLT})") (class "Default")
      (node (ref "TP1") (pin "1") (pinfunction "1_1") (pintype "passive"))
      (node (ref "U4") (pin "6") (pinfunction "~{FLT}_6") (pintype "bidirectional"))
    )
    (net (code "51") (name "Net-(U5-PG)") (class "Default")
      (node (ref "TP16") (pin "1") (pinfunction "1_1") (pintype "passive"))
      (node (ref "U5") (pin "13") (pinfunction "PG_13") (pintype "open_collector"))
    )
    (net (code "52") (name "Net-(U5-SYNC)") (class "Default")
      (node (ref "R10") (pin "2") (pinfunction "2_2") (pintype "passive"))
      (node (ref "R7") (pin "1") (pinfunction "1_1") (pintype "passive"))
      (node (ref "TP19") (pin "1") (pinfunction "1_1") (pintype "passive"))
      (node (ref "U5") (pin "5") (pinfunction "SYNC_5") (pintype "input"))
    )
    (net (code "53") (name "Net-(U6-SET0)") (class "Default")
      (node (ref "C15") (pin "1") (pinfunction "1_1") (pintype "passive"))
      (node (ref "C18") (pin "1") (pinfunction "1_1") (pintype "passive"))
      (node (ref "R19") (pin "1") (pinfunction "1_1") (pintype "passive"))
      (node (ref "U6") (pin "4") (pinfunction "SET0_4") (pintype "input"))
      (node (ref "U6") (pin "8") (pinfunction "VCC_8") (pintype "power_in"))
    )
    (net (code "54") (name "Net-(U7-BOOT0)") (class "Default")
      (node (ref "R17") (pin "2") (pinfunction "2_2") (pintype "passive"))
      (node (ref "TP15") (pin "1") (pinfunction "1_1") (pintype "passive"))
      (node (ref "U7") (pin "60") (pinfunction "BOOT0_60") (pintype "bidirectional"))
    )
    (net (code "55") (name "Net-(U7-PH0-OSC_IN)") (class "Default")
      (node (ref "C16") (pin "1") (pinfunction "1_1") (pintype "passive"))
      (node (ref "U7") (pin "5") (pinfunction "PH0-OSC_IN_5") (pintype "bidirectional"))
      (node (ref "X1") (pin "1") (pinfunction "1_1") (pintype "passive"))
    )
    (net (code "56") (name "Net-(U7-PH1-OSC_OUT)") (class "Default")
      (node (ref "C11") (pin "1") (pinfunction "1_1") (pintype "passive"))
      (node (ref "U7") (pin "6") (pinfunction "PH1-OSC_OUT_6") (pintype "bidirectional"))
      (node (ref "X1") (pin "3") (pinfunction "2_3") (pintype "passive"))
    )
    (net (code "57") (name "Net-(U11-ANTN)") (class "Default")
      (node (ref "C42") (pin "2") (pinfunction "2_2") (pintype "passive"))
      (node (ref "L7") (pin "2") (pinfunction "2_2") (pintype "passive"))
      (node (ref "U11") (pin "4") (pinfunction "ANTN_4") (pintype "bidirectional"))
    )
    (net (code "58") (name "Net-(U11-ANTP)") (class "Default")
      (node (ref "C43") (pin "2") (pinfunction "2_2") (pintype "passive"))
      (node (ref "L6") (pin "2") (pinfunction "2_2") (pintype "passive"))
      (node (ref "L8") (pin "1") (pinfunction "1_1") (pintype "passive"))
      (node (ref "U11") (pin "3") (pinfunction "ANTP_3") (pintype "bidirectional"))
    )
    (net (code "59") (name "Net-(U11-ANTP1)") (class "Default")
      (node (ref "C49") (pin "2") (pinfunction "2_2") (pintype "passive"))
      (node (ref "L9") (pin "2") (pinfunction "2_2") (pintype "passive"))
      (node (ref "U11") (pin "5") (pinfunction "ANTP1_5") (pintype "bidirectional"))
    )
    (net (code "60") (name "Net-(U11-CLK16N)") (class "Default")
      (node (ref "C44") (pin "1") (pinfunction "1_1") (pintype "passive"))
      (node (ref "R28") (pin "1") (pinfunction "1_1") (pintype "passive"))
      (node (ref "U11") (pin "27") (pinfunction "CLK16N_27") (pintype "passive"))
    )
    (net (code "61") (name "Net-(U11-CLK16P)") (class "Default")
      (node (ref "C45") (pin "1") (pinfunction "1_1") (pintype "passive"))
      (node (ref "R28") (pin "2") (pinfunction "2_2") (pintype "passive"))
      (node (ref "U11") (pin "28") (pinfunction "CLK16P_28") (pintype "passive"))
    )
    (net (code "62") (name "Net-(U11-CS)") (class "Default")
      (node (ref "J15") (pin "1") (pinfunction "1_1") (pintype "passive"))
      (node (ref "U11") (pin "14") (pinfunction "CS_14") (pintype "input"))
    )
    (net (code "63") (name "Net-(U11-IRQ)") (class "Default")
      (node (ref "J15") (pin "9") (pinfunction "9_9") (pintype "passive"))
      (node (ref "U11") (pin "19") (pinfunction "IRQ_19") (pintype "bidirectional"))
    )
    (net (code "64") (name "Net-(U11-L1)") (class "Default")
      (node (ref "U11") (pin "10") (pinfunction "L1_10") (pintype "input"))
      (node (ref "U11") (pin "9") (pinfunction "L2_9") (pintype "input"))
    )
    (net (code "65") (name "Net-(U11-MISO)") (class "Default")
      (node (ref "J15") (pin "5") (pinfunction "5_5") (pintype "passive"))
      (node (ref "U11") (pin "16") (pinfunction "MISO_16") (pintype "output"))
    )
    (net (code "66") (name "Net-(U11-MOSI)") (class "Default")
      (node (ref "J15") (pin "7") (pinfunction "7_7") (pintype "passive"))
      (node (ref "U11") (pin "17") (pinfunction "MOSI_17") (pintype "input"))
    )
    (net (code "67") (name "Net-(U11-PWRAMP)") (class "Default")
      (node (ref "J15") (pin "11") (pinfunction "11_11") (pintype "passive"))
      (node (ref "U11") (pin "20") (pinfunction "PWRAMP_20") (pintype "bidirectional"))
    )
    (net (code "68") (name "Net-(U11-SCLK)") (class "Default")
      (node (ref "J15") (pin "3") (pinfunction "3_3") (pintype "passive"))
      (node (ref "U11") (pin "15") (pinfunction "SCLK_15") (pintype "input"))
    )
    (net (code "69") (name "Net-(U11-VDD_A1)") (class "Default")
      (node (ref "C46") (pin "1") (pinfunction "1_1") (pintype "passive"))
      (node (ref "U11") (pin "1") (pinfunction "VDD_A1_1") (pintype "power_in"))
    )
    (net (code "70") (name "Net-(U11-VDD_A2)") (class "Default")
      (node (ref "C47") (pin "2") (pinfunction "2_2") (pintype "passive"))
      (node (ref "U11") (pin "7") (pinfunction "VDD_A2_7") (pintype "power_in"))
    )
    (net (code "71") (name "Net-(U11-VDD_IO)") (class "Default")
      (node (ref "C53") (pin "1") (pinfunction "1_1") (pintype "passive"))
      (node (ref "C54") (pin "1") (pinfunction "1_1") (pintype "passive"))
      (node (ref "C55") (pin "1") (pinfunction "1_1") (pintype "passive"))
      (node (ref "R33") (pin "1") (pinfunction "1_1") (pintype "passive"))
      (node (ref "U11") (pin "23") (pinfunction "VDD_IO_23") (pintype "power_in"))
    )
    (net (code "72") (name "Net-(U12-BYPASS)") (class "Default")
      (node (ref "C56") (pin "1") (pinfunction "1_1") (pintype "passive"))
      (node (ref "U12") (pin "4") (pinfunction "BYPASS_4") (pintype "power_in"))
    )
    (net (code "73") (name "Net-(U12-EN)") (class "Default")
      (node (ref "C57") (pin "1") (pinfunction "1_1") (pintype "passive"))
      (node (ref "R32") (pin "2") (pinfunction "2_2") (pintype "passive"))
      (node (ref "U12") (pin "1") (pinfunction "VIN_1") (pintype "power_in"))
      (node (ref "U12") (pin "3") (pinfunction "EN_3") (pintype "input"))
    )
    (net (code "74") (name "Net-(U12-VOUT)") (class "Default")
      (node (ref "C50") (pin "1") (pinfunction "1_1") (pintype "passive"))
      (node (ref "C51") (pin "1") (pinfunction "1_1") (pintype "passive"))
      (node (ref "C52") (pin "1") (pinfunction "1_1") (pintype "passive"))
      (node (ref "U12") (pin "5") (pinfunction "VOUT_5") (pintype "power_in"))
      (node (ref "X3") (pin "4") (pinfunction "VDD_4") (pintype "power_in"))
    )
    (net (code "75") (name "Net-(U13-ANTN)") (class "Default")
      (node (ref "C58") (pin "2") (pinfunction "2_2") (pintype "passive"))
      (node (ref "L11") (pin "2") (pinfunction "2_2") (pintype "passive"))
      (node (ref "U13") (pin "4") (pinfunction "ANTN_4") (pintype "bidirectional"))
    )
    (net (code "76") (name "Net-(U13-ANTP)") (class "Default")
      (node (ref "C59") (pin "2") (pinfunction "2_2") (pintype "passive"))
      (node (ref "L10") (pin "2") (pinfunction "2_2") (pintype "passive"))
      (node (ref "L12") (pin "1") (pinfunction "1_1") (pintype "passive"))
      (node (ref "U13") (pin "3") (pinfunction "ANTP_3") (pintype "bidirectional"))
    )
    (net (code "77") (name "Net-(U13-ANTP1)") (class "Default")
      (node (ref "C65") (pin "2") (pinfunction "2_2") (pintype "passive"))
      (node (ref "L13") (pin "2") (pinfunction "2_2") (pintype "passive"))
      (node (ref "U13") (pin "5") (pinfunction "ANTP1_5") (pintype "bidirectional"))
    )
    (net (code "78") (name "Net-(U13-CLK16N)") (class "Default")
      (node (ref "C60") (pin "1") (pinfunction "1_1") (pintype "passive"))
      (node (ref "R34") (pin "1") (pinfunction "1_1") (pintype "passive"))
      (node (ref "U13") (pin "27") (pinfunction "CLK16N_27") (pintype "passive"))
    )
    (net (code "79") (name "Net-(U13-CLK16P)") (class "Default")
      (node (ref "C61") (pin "1") (pinfunction "1_1") (pintype "passive"))
      (node (ref "R34") (pin "2") (pinfunction "2_2") (pintype "passive"))
      (node (ref "U13") (pin "28") (pinfunction "CLK16P_28") (pintype "passive"))
    )
    (net (code "80") (name "Net-(U13-CS)") (class "Default")
      (node (ref "J19") (pin "1") (pinfunction "1_1") (pintype "passive"))
      (node (ref "U13") (pin "14") (pinfunction "CS_14") (pintype "input"))
    )
    (net (code "81") (name "Net-(U13-IRQ)") (class "Default")
      (node (ref "J19") (pin "9") (pinfunction "9_9") (pintype "passive"))
      (node (ref "U13") (pin "19") (pinfunction "IRQ_19") (pintype "bidirectional"))
    )
    (net (code "82") (name "Net-(U13-L1)") (class "Default")
      (node (ref "U13") (pin "10") (pinfunction "L1_10") (pintype "input"))
      (node (ref "U13") (pin "9") (pinfunction "L2_9") (pintype "input"))
    )
    (net (code "83") (name "Net-(U13-MISO)") (class "Default")
      (node (ref "J19") (pin "5") (pinfunction "5_5") (pintype "passive"))
      (node (ref "U13") (pin "16") (pinfunction "MISO_16") (pintype "output"))
    )
    (net (code "84") (name "Net-(U13-MOSI)") (class "Default")
      (node (ref "J19") (pin "7") (pinfunction "7_7") (pintype "passive"))
      (node (ref "U13") (pin "17") (pinfunction "MOSI_17") (pintype "input"))
    )
    (net (code "85") (name "Net-(U13-PWRAMP)") (class "Default")
      (node (ref "J19") (pin "11") (pinfunction "11_11") (pintype "passive"))
      (node (ref "U13") (pin "20") (pinfunction "PWRAMP_20") (pintype "bidirectional"))
    )
    (net (code "86") (name "Net-(U13-SCLK)") (class "Default")
      (node (ref "J19") (pin "3") (pinfunction "3_3") (pintype "passive"))
      (node (ref "U13") (pin "15") (pinfunction "SCLK_15") (pintype "input"))
    )
    (net (code "87") (name "Net-(U13-VDD_A1)") (class "Default")
      (node (ref "C62") (pin "1") (pinfunction "1_1") (pintype "passive"))
      (node (ref "U13") (pin "1") (pinfunction "VDD_A1_1") (pintype "power_in"))
    )
    (net (code "88") (name "Net-(U13-VDD_A2)") (class "Default")
      (node (ref "C63") (pin "2") (pinfunction "2_2") (pintype "passive"))
      (node (ref "U13") (pin "7") (pinfunction "VDD_A2_7") (pintype "power_in"))
    )
    (net (code "89") (name "Net-(U13-VDD_IO)") (class "Default")
      (node (ref "C69") (pin "1") (pinfunction "1_1") (pintype "passive"))
      (node (ref "C70") (pin "1") (pinfunction "1_1") (pintype "passive"))
      (node (ref "C71") (pin "1") (pinfunction "1_1") (pintype "passive"))
      (node (ref "R40") (pin "1") (pinfunction "1_1") (pintype "passive"))
      (node (ref "U13") (pin "23") (pinfunction "VDD_IO_23") (pintype "power_in"))
    )
    (net (code "90") (name "Net-(U14-BYPASS)") (class "Default")
      (node (ref "C72") (pin "1") (pinfunction "1_1") (pintype "passive"))
      (node (ref "U14") (pin "4") (pinfunction "BYPASS_4") (pintype "power_in"))
    )
    (net (code "91") (name "Net-(U14-EN)") (class "Default")
      (node (ref "C73") (pin "1") (pinfunction "1_1") (pintype "passive"))
      (node (ref "R39") (pin "2") (pinfunction "2_2") (pintype "passive"))
      (node (ref "U14") (pin "1") (pinfunction "VIN_1") (pintype "power_in"))
      (node (ref "U14") (pin "3") (pinfunction "EN_3") (pintype "input"))
    )
    (net (code "92") (name "Net-(U14-VOUT)") (class "Default")
      (node (ref "C66") (pin "1") (pinfunction "1_1") (pintype "passive"))
      (node (ref "C67") (pin "1") (pinfunction "1_1") (pintype "passive"))
      (node (ref "C68") (pin "1") (pinfunction "1_1") (pintype "passive"))
      (node (ref "U14") (pin "5") (pinfunction "VOUT_5") (pintype "power_in"))
      (node (ref "X4") (pin "4") (pinfunction "VDD_4") (pintype "power_in"))
    )
    (net (code "93") (name "Net-(X3-OUT)") (class "Default")
      (node (ref "C45") (pin "2") (pinfunction "2_2") (pintype "passive"))
      (node (ref "X3") (pin "3") (pinfunction "OUT_3") (pintype "output"))
    )
    (net (code "94") (name "Net-(X4-OUT)") (class "Default")
      (node (ref "C61") (pin "2") (pinfunction "2_2") (pintype "passive"))
      (node (ref "X4") (pin "3") (pinfunction "OUT_3") (pintype "output"))
    )
    (net (code "95") (name "OPD_ISET") (class "Default")
      (node (ref "R24") (pin "1") (pinfunction "1_1") (pintype "passive"))
      (node (ref "R36") (pin "2") (pinfunction "2_2") (pintype "passive"))
      (node (ref "TP14") (pin "1") (pinfunction "1_1") (pintype "passive"))
      (node (ref "U1") (pin "5") (pinfunction "SET_5") (pintype "input"))
    )
    (net (code "96") (name "OPD_ISET_IN") (class "Default")
      (node (ref "R24") (pin "2") (pinfunction "2_2") (pintype "passive"))
      (node (ref "U7") (pin "27") (pinfunction "PB1_27") (pintype "bidirectional"))
    )
    (net (code "97") (name "OPD_PWR") (class "Default")
      (node (ref "C4") (pin "1") (pinfunction "1_1") (pintype "passive"))
      (node (ref "J6") (pin "15") (pinfunction "15_15") (pintype "passive"))
      (node (ref "J6") (pin "16") (pinfunction "16_16") (pintype "passive"))
      (node (ref "JP1") (pin "5") (pinfunction "5_5") (pintype "passive"))
      (node (ref "JP1") (pin "6") (pinfunction "6_6") (pintype "passive"))
      (node (ref "R11") (pin "1") (pinfunction "1_1") (pintype "passive"))
      (node (ref "R4") (pin "2") (pinfunction "2_2") (pintype "passive"))
      (node (ref "R8") (pin "1") (pinfunction "1_1") (pintype "passive"))
      (node (ref "U1") (pin "7") (pinfunction "OUT_2_7") (pintype "power_in"))
      (node (ref "U1") (pin "8") (pinfunction "OUT_8") (pintype "power_in"))
    )
    (net (code "98") (name "OPD_SCL") (class "Default")
      (node (ref "J6") (pin "13") (pinfunction "13_13") (pintype "passive"))
      (node (ref "J6") (pin "14") (pinfunction "14_14") (pintype "passive"))
      (node (ref "JP1") (pin "3") (pinfunction "3_3") (pintype "passive"))
      (node (ref "JP1") (pin "4") (pinfunction "4_4") (pintype "passive"))
      (node (ref "R8") (pin "2") (pinfunction "2_2") (pintype "passive"))
      (node (ref "U7") (pin "61") (pinfunction "PB8_61") (pintype "bidirectional"))
    )
    (net (code "99") (name "OPD_SDA") (class "Default")
      (node (ref "J6") (pin "11") (pinfunction "11_11") (pintype "passive"))
      (node (ref "J6") (pin "12") (pinfunction "12_12") (pintype "passive"))
      (node (ref "JP1") (pin "1") (pinfunction "1_1") (pintype "passive"))
      (node (ref "JP1") (pin "2") (pinfunction "2_2") (pintype "passive"))
      (node (ref "R11") (pin "2") (pinfunction "2_2") (pintype "passive"))
      (node (ref "U7") (pin "62") (pinfunction "PB9_62") (pintype "bidirectional"))
    )
    (net (code "100") (name "OPD_~{FAULT}") (class "Default")
      (node (ref "R16") (pin "1") (pinfunction "1_1") (pintype "passive"))
      (node (ref "TP8") (pin "1") (pinfunction "1_1") (pintype "passive"))
      (node (ref "U1") (pin "6") (pinfunction "~{FAULT}_6") (pintype "output"))
      (node (ref "U7") (pin "55") (pinfunction "PB3_55") (pintype "bidirectional"))
    )
    (net (code "101") (name "OSC32_IN") (class "Default")
      (node (ref "U7") (pin "3") (pinfunction "PC14-OSC32_IN_3") (pintype "bidirectional"))
    )
    (net (code "102") (name "OSC32_OUT") (class "Default")
      (node (ref "U7") (pin "4") (pinfunction "PC15-OSC32_OUT_4") (pintype "bidirectional"))
    )
    (net (code "103") (name "PA1") (class "Default")
      (node (ref "TP5") (pin "1") (pinfunction "1_1") (pintype "passive"))
      (node (ref "U7") (pin "15") (pinfunction "PA1_15") (pintype "bidirectional"))
    )
    (net (code "104") (name "PA15") (class "Default")
      (node (ref "TP6") (pin "1") (pinfunction "1_1") (pintype "passive"))
      (node (ref "U7") (pin "50") (pinfunction "PA15_50") (pintype "bidirectional"))
    )
    (net (code "105") (name "PB10") (class "Default")
      (node (ref "TP4") (pin "1") (pinfunction "1_1") (pintype "passive"))
      (node (ref "U7") (pin "29") (pinfunction "PB10_29") (pintype "bidirectional"))
    )
    (net (code "106") (name "PB12") (class "Default")
      (node (ref "U7") (pin "33") (pinfunction "PB12_33") (pintype "bidirectional"))
    )
    (net (code "107") (name "PC0") (class "Default")
      (node (ref "U7") (pin "8") (pinfunction "PC0_8") (pintype "bidirectional"))
    )
    (net (code "108") (name "PC1") (class "Default")
      (node (ref "U7") (pin "9") (pinfunction "PC1_9") (pintype "bidirectional"))
    )
    (net (code "109") (name "PC2") (class "Default")
      (node (ref "U7") (pin "10") (pinfunction "PC2_10") (pintype "bidirectional"))
    )
    (net (code "110") (name "PC3") (class "Default")
      (node (ref "U7") (pin "11") (pinfunction "PC3_11") (pintype "bidirectional"))
    )
    (net (code "111") (name "PC4") (class "Default")
      (node (ref "U7") (pin "24") (pinfunction "PC4_24") (pintype "bidirectional"))
    )
    (net (code "112") (name "PC5") (class "Default")
      (node (ref "U7") (pin "25") (pinfunction "PC5_25") (pintype "bidirectional"))
    )
    (net (code "113") (name "RADIO1_CS") (class "Default")
      (node (ref "J15") (pin "2") (pinfunction "2_2") (pintype "passive"))
      (node (ref "U7") (pin "37") (pinfunction "PC6_37") (pintype "bidirectional"))
    )
    (net (code "114") (name "RADIO1_IRQ") (class "Default")
      (node (ref "J15") (pin "10") (pinfunction "10_10") (pintype "passive"))
      (node (ref "U7") (pin "20") (pinfunction "PA4_20") (pintype "bidirectional"))
    )
    (net (code "115") (name "RADIO1_PTT") (class "Default")
      (node (ref "J15") (pin "12") (pinfunction "12_12") (pintype "passive"))
    )
    (net (code "116") (name "RADIO2_CS") (class "Default")
      (node (ref "J19") (pin "2") (pinfunction "2_2") (pintype "passive"))
      (node (ref "U7") (pin "38") (pinfunction "PC7_38") (pintype "bidirectional"))
    )
    (net (code "117") (name "RADIO2_IRQ") (class "Default")
      (node (ref "J19") (pin "10") (pinfunction "10_10") (pintype "passive"))
      (node (ref "U7") (pin "41") (pinfunction "PA8_41") (pintype "bidirectional"))
    )
    (net (code "118") (name "RADIO2_PTT") (class "Default")
      (node (ref "J19") (pin "12") (pinfunction "12_12") (pintype "passive"))
    )
    (net (code "119") (name "SD") (class "Default")
      (node (ref "J6") (pin "39") (pinfunction "39_39") (pintype "passive"))
      (node (ref "J6") (pin "40") (pinfunction "40_40") (pintype "passive"))
      (node (ref "JP10") (pin "10") (pinfunction "10_10") (pintype "passive"))
      (node (ref "JP10") (pin "9") (pinfunction "9_9") (pintype "passive"))
      (node (ref "R13") (pin "2") (pinfunction "2_2") (pintype "passive"))
      (node (ref "U6") (pin "7") (pinfunction "~{WDO}_7") (pintype "output"))
    )
    (net (code "120") (name "SDIO_CK") (class "Default")
      (node (ref "R14") (pin "2") (pinfunction "22_2") (pintype "passive"))
      (node (ref "TP7") (pin "1") (pinfunction "1_1") (pintype "passive"))
      (node (ref "U7") (pin "53") (pinfunction "PC12_53") (pintype "bidirectional"))
      (node (ref "U9") (pin "M6") (pinfunction "SCK_M6") (pintype "input"))
    )
    (net (code "121") (name "SDIO_CMD") (class "Default")
      (node (ref "R14") (pin "9") (pinfunction "99_9") (pintype "passive"))
      (node (ref "U7") (pin "54") (pinfunction "PD2_54") (pintype "bidirectional"))
      (node (ref "U9") (pin "M5") (pinfunction "CMD_M5") (pintype "input"))
    )
    (net (code "122") (name "SDIO_D0") (class "Default")
      (node (ref "R15") (pin "1") (pinfunction "11_1") (pintype "passive"))
      (node (ref "U7") (pin "39") (pinfunction "PC8_39") (pintype "bidirectional"))
      (node (ref "U9") (pin "A3") (pinfunction "D0_A3") (pintype "input"))
    )
    (net (code "123") (name "SDIO_D1") (class "Default")
      (node (ref "R15") (pin "9") (pinfunction "99_9") (pintype "passive"))
      (node (ref "U7") (pin "40") (pinfunction "PC9_40") (pintype "bidirectional"))
      (node (ref "U9") (pin "A4") (pinfunction "D1_A4") (pintype "input"))
    )
    (net (code "124") (name "SDIO_D2") (class "Default")
      (node (ref "R15") (pin "2") (pinfunction "22_2") (pintype "passive"))
      (node (ref "U7") (pin "51") (pinfunction "PC10_51") (pintype "bidirectional"))
      (node (ref "U9") (pin "A5") (pinfunction "D2_A5") (pintype "input"))
    )
    (net (code "125") (name "SDIO_D3") (class "Default")
      (node (ref "R14") (pin "7") (pinfunction "77_7") (pintype "passive"))
      (node (ref "U7") (pin "52") (pinfunction "PC11_52") (pintype "bidirectional"))
      (node (ref "U9") (pin "A1") (pinfunction "D3_A1") (pintype "input"))
      (node (ref "U9") (pin "B2") (pinfunction "D3_B2") (pintype "input"))
    )
    (net (code "126") (name "SDIO_D4") (class "Default")
      (node (ref "R14") (pin "6") (pinfunction "66_6") (pintype "passive"))
      (node (ref "U9") (pin "A2") (pinfunction "D4_A2") (pintype "input"))
      (node (ref "U9") (pin "B3") (pinfunction "D4_B3") (pintype "input"))
    )
    (net (code "127") (name "SDIO_D5") (class "Default")
      (node (ref "R14") (pin "8") (pinfunction "88_8") (pintype "passive"))
      (node (ref "U9") (pin "B4") (pinfunction "D5_B4") (pintype "input"))
      (node (ref "U9") (pin "C3") (pinfunction "D5_C3") (pintype "input"))
      (node (ref "U9") (pin "D3") (pinfunction "D5_D3") (pintype "input"))
    )
    (net (code "128") (name "SDIO_D6") (class "Default")
      (node (ref "R14") (pin "4") (pinfunction "44_4") (pintype "passive"))
      (node (ref "U9") (pin "B5") (pinfunction "D6_B5") (pintype "bidirectional"))
      (node (ref "U9") (pin "C5") (pinfunction "D6_C5") (pintype "bidirectional"))
    )
    (net (code "129") (name "SDIO_D7") (class "Default")
      (node (ref "R15") (pin "3") (pinfunction "33_3") (pintype "passive"))
      (node (ref "U9") (pin "B6") (pinfunction "D7_B6") (pintype "input"))
      (node (ref "U9") (pin "C7") (pinfunction "D7_C7") (pintype "input"))
    )
    (net (code "130") (name "SDIO_RST") (class "Default")
      (node (ref "R14") (pin "3") (pinfunction "33_3") (pintype "passive"))
      (node (ref "U9") (pin "K5") (pinfunction "~{RST}_K5") (pintype "input"))
    )
    (net (code "131") (name "SPI1_MISO") (class "Default")
      (node (ref "J15") (pin "6") (pinfunction "6_6") (pintype "passive"))
      (node (ref "J19") (pin "6") (pinfunction "6_6") (pintype "passive"))
      (node (ref "TP22") (pin "1") (pinfunction "1_1") (pintype "passive"))
      (node (ref "U7") (pin "22") (pinfunction "PA6_22") (pintype "bidirectional"))
    )
    (net (code "132") (name "SPI1_MOSI") (class "Default")
      (node (ref "J15") (pin "8") (pinfunction "8_8") (pintype "passive"))
      (node (ref "J19") (pin "8") (pinfunction "8_8") (pintype "passive"))
      (node (ref "TP18") (pin "1") (pinfunction "1_1") (pintype "passive"))
      (node (ref "U7") (pin "23") (pinfunction "PA7_23") (pintype "bidirectional"))
    )
    (net (code "133") (name "SPI1_SCK") (class "Default")
      (node (ref "J15") (pin "4") (pinfunction "4_4") (pintype "passive"))
      (node (ref "J19") (pin "4") (pinfunction "4_4") (pintype "passive"))
      (node (ref "TP23") (pin "1") (pinfunction "1_1") (pintype "passive"))
      (node (ref "U7") (pin "21") (pinfunction "PA5_21") (pintype "bidirectional"))
    )
    (net (code "134") (name "SPI2_MISO") (class "Default")
      (node (ref "U7") (pin "35") (pinfunction "PB14_35") (pintype "bidirectional"))
    )
    (net (code "135") (name "SPI2_MOSI") (class "Default")
      (node (ref "U7") (pin "36") (pinfunction "PB15_36") (pintype "bidirectional"))
    )
    (net (code "136") (name "SPI2_SCK") (class "Default")
      (node (ref "U7") (pin "34") (pinfunction "PB13_34") (pintype "bidirectional"))
    )
    (net (code "137") (name "SWCLK") (class "Default")
      (node (ref "J7") (pin "4") (pinfunction "SWDCLK/TCK_4") (pintype "passive"))
      (node (ref "U7") (pin "49") (pinfunction "PA14_49") (pintype "bidirectional"))
    )
    (net (code "138") (name "SWDIO") (class "Default")
      (node (ref "J7") (pin "2") (pinfunction "SWDIO/TMS_2") (pintype "passive"))
      (node (ref "U7") (pin "46") (pinfunction "PA13_46") (pintype "bidirectional"))
    )
    (net (code "139") (name "SYSCLK1") (class "Default")
      (node (ref "J8") (pin "FEED") (pinfunction "SIGNAL_FEED") (pintype "bidirectional"))
      (node (ref "U11") (pin "13") (pinfunction "SYSCLK_13") (pintype "bidirectional"))
    )
    (net (code "140") (name "USART2_RX") (class "Default")
      (node (ref "U$2") (pin "P$3") (pinfunction "TXO_P$3") (pintype "passive"))
      (node (ref "U7") (pin "17") (pinfunction "PA3_17") (pintype "bidirectional"))
    )
    (net (code "141") (name "USART2_TX") (class "Default")
      (node (ref "U$2") (pin "P$2") (pinfunction "RXI_P$2") (pintype "passive"))
      (node (ref "U7") (pin "16") (pinfunction "PA2_16") (pintype "bidirectional"))
    )
    (net (code "142") (name "VBUS") (class "Default")
      (node (ref "C1") (pin "1") (pinfunction "1_1") (pintype "passive"))
      (node (ref "J6") (pin "21") (pinfunction "21_21") (pintype "passive"))
      (node (ref "J6") (pin "22") (pinfunction "22_22") (pintype "passive"))
      (node (ref "J6") (pin "23") (pinfunction "23_23") (pintype "passive"))
      (node (ref "J6") (pin "24") (pinfunction "24_24") (pintype "passive"))
      (node (ref "J6") (pin "25") (pinfunction "25_25") (pintype "passive"))
      (node (ref "J6") (pin "26") (pinfunction "26_26") (pintype "passive"))
      (node (ref "JP10") (pin "1") (pinfunction "1_1") (pintype "passive"))
      (node (ref "JP10") (pin "2") (pinfunction "2_2") (pintype "passive"))
      (node (ref "JP10") (pin "3") (pinfunction "3_3") (pintype "passive"))
      (node (ref "JP10") (pin "4") (pinfunction "4_4") (pintype "passive"))
      (node (ref "R5") (pin "2") (pinfunction "2_2") (pintype "passive"))
      (node (ref "U4") (pin "4") (pinfunction "VIN_4") (pintype "power_in"))
    )
    (net (code "143") (name "VBUSP") (class "Default")
      (node (ref "C10") (pin "1") (pinfunction "1_1") (pintype "passive"))
      (node (ref "C7") (pin "1") (pinfunction "1_1") (pintype "passive"))
      (node (ref "JP8") (pin "1") (pinfunction "1_1") (pintype "passive"))
      (node (ref "R1") (pin "2") (pinfunction "2_2") (pintype "passive"))
      (node (ref "R7") (pin "2") (pinfunction "2_2") (pintype "passive"))
      (node (ref "TP20") (pin "1") (pinfunction "1_1") (pintype "passive"))
      (node (ref "U4") (pin "5") (pinfunction "VOUT_5") (pintype "power_in"))
      (node (ref "U5") (pin "2") (pinfunction "VIN_2") (pintype "power_in"))
      (node (ref "U5") (pin "3") (pinfunction "VIN_3") (pintype "power_in"))
      (node (ref "U5") (pin "4") (pinfunction "EN_4") (pintype "input"))
      (node (ref "U5") (pin "8") (pinfunction "VIN_8") (pintype "power_in"))
    )
    (net (code "144") (name "VCAP") (class "Default")
      (node (ref "C14") (pin "1") (pinfunction "1_1") (pintype "passive"))
      (node (ref "U7") (pin "30") (pinfunction "VCAP_1_30") (pintype "bidirectional"))
    )
    (net (code "145") (name "VDDI") (class "Default")
      (node (ref "C19") (pin "1") (pinfunction "1_1") (pintype "passive"))
      (node (ref "C21") (pin "1") (pinfunction "1_1") (pintype "passive"))
      (node (ref "U9") (pin "C1") (pinfunction "VDDI_C1") (pintype "power_in"))
      (node (ref "U9") (pin "C2") (pinfunction "VDDI_C2") (pintype "power_in"))
    )
    (net (code "146") (name "WDT") (class "Default")
      (node (ref "R3") (pin "2") (pinfunction "2_2") (pintype "passive"))
      (node (ref "TP3") (pin "1") (pinfunction "1_1") (pintype "passive"))
      (node (ref "U6") (pin "1") (pinfunction "WDI_1") (pintype "input"))
      (node (ref "U7") (pin "14") (pinfunction "PA0_14") (pintype "bidirectional"))
    )
    (net (code "147") (name "unconnected-(J6-Pad1)") (class "Default")
      (node (ref "J6") (pin "1") (pinfunction "1_1") (pintype "passive"))
    )
    (net (code "148") (name "unconnected-(J6-Pad2)") (class "Default")
      (node (ref "J6") (pin "2") (pinfunction "2_2") (pintype "passive"))
    )
    (net (code "149") (name "unconnected-(J6-Pad3)") (class "Default")
      (node (ref "J6") (pin "3") (pinfunction "3_3") (pintype "passive"))
    )
    (net (code "150") (name "unconnected-(J6-Pad4)") (class "Default")
      (node (ref "J6") (pin "4") (pinfunction "4_4") (pintype "passive"))
    )
    (net (code "151") (name "unconnected-(J6-Pad5)") (class "Default")
      (node (ref "J6") (pin "5") (pinfunction "5_5") (pintype "passive"))
    )
    (net (code "152") (name "unconnected-(J6-Pad6)") (class "Default")
      (node (ref "J6") (pin "6") (pinfunction "6_6") (pintype "passive"))
    )
    (net (code "153") (name "unconnected-(J6-Pad7)") (class "Default")
      (node (ref "J6") (pin "7") (pinfunction "7_7") (pintype "passive"))
    )
    (net (code "154") (name "unconnected-(J6-Pad8)") (class "Default")
      (node (ref "J6") (pin "8") (pinfunction "8_8") (pintype "passive"))
    )
    (net (code "155") (name "unconnected-(J6-Pad9)") (class "Default")
      (node (ref "J6") (pin "9") (pinfunction "9_9") (pintype "passive"))
    )
    (net (code "156") (name "unconnected-(J6-Pad10)") (class "Default")
      (node (ref "J6") (pin "10") (pinfunction "10_10") (pintype "passive"))
    )
    (net (code "157") (name "unconnected-(J7-NC{slash}TDI-Pad8)") (class "Default")
      (node (ref "J7") (pin "8") (pinfunction "NC/TDI_8") (pintype "passive"))
    )
    (net (code "158") (name "unconnected-(J7-SWO{slash}TDO-Pad6)") (class "Default")
      (node (ref "J7") (pin "6") (pinfunction "SWO/TDO_6") (pintype "passive"))
    )
    (net (code "159") (name "unconnected-(R14-11-Pad1)") (class "Default")
      (node (ref "R14") (pin "1") (pinfunction "11_1") (pintype "passive"))
    )
    (net (code "160") (name "unconnected-(R15-44-Pad4)") (class "Default")
      (node (ref "R15") (pin "4") (pinfunction "44_4") (pintype "passive"))
    )
    (net (code "161") (name "unconnected-(R15-77-Pad7)") (class "Default")
      (node (ref "R15") (pin "7") (pinfunction "77_7") (pintype "passive"))
    )
    (net (code "162") (name "unconnected-(R15-88-Pad8)") (class "Default")
      (node (ref "R15") (pin "8") (pinfunction "88_8") (pintype "passive"))
    )
    (net (code "163") (name "unconnected-(U$2-CTS-PadP$5)") (class "Default")
      (node (ref "U$2") (pin "P$5") (pinfunction "CTS_P$5") (pintype "passive"))
    )
    (net (code "164") (name "unconnected-(U$2-DTR-PadP$1)") (class "Default")
      (node (ref "U$2") (pin "P$1") (pinfunction "DTR_P$1") (pintype "passive"))
    )
    (net (code "165") (name "unconnected-(U4-DV{slash}DT-Pad2)") (class "Default")
      (node (ref "U4") (pin "2") (pinfunction "DV/DT_2") (pintype "bidirectional"))
    )
    (net (code "166") (name "unconnected-(U4-OVLO-Pad8)") (class "Default")
      (node (ref "U4") (pin "8") (pinfunction "OVLO_8") (pintype "bidirectional"))
    )
    (net (code "167") (name "unconnected-(U6-NC-Pad3)") (class "Default")
      (node (ref "U6") (pin "3") (pinfunction "NC_3") (pintype "no_connect"))
    )
    (net (code "168") (name "unconnected-(U11-ANTSEL-Pad21)") (class "Default")
      (node (ref "U11") (pin "21") (pinfunction "ANTSEL_21") (pintype "bidirectional"))
    )
    (net (code "169") (name "unconnected-(U11-DATA-Pad11)") (class "Default")
      (node (ref "U11") (pin "11") (pinfunction "DATA_11") (pintype "bidirectional"))
    )
    (net (code "170") (name "unconnected-(U11-DCLK-Pad12)") (class "Default")
      (node (ref "U11") (pin "12") (pinfunction "DCLK_12") (pintype "bidirectional"))
    )
    (net (code "171") (name "unconnected-(U11-FILT-Pad8)") (class "Default")
      (node (ref "U11") (pin "8") (pinfunction "FILT_8") (pintype "output"))
    )
    (net (code "172") (name "unconnected-(U13-ANTSEL-Pad21)") (class "Default")
      (node (ref "U13") (pin "21") (pinfunction "ANTSEL_21") (pintype "bidirectional"))
    )
    (net (code "173") (name "unconnected-(U13-DATA-Pad11)") (class "Default")
      (node (ref "U13") (pin "11") (pinfunction "DATA_11") (pintype "bidirectional"))
    )
    (net (code "174") (name "unconnected-(U13-DCLK-Pad12)") (class "Default")
      (node (ref "U13") (pin "12") (pinfunction "DCLK_12") (pintype "bidirectional"))
    )
    (net (code "175") (name "unconnected-(U13-FILT-Pad8)") (class "Default")
      (node (ref "U13") (pin "8") (pinfunction "FILT_8") (pintype "output"))
    )
    (net (code "176") (name "unconnected-(X3-VCTRL-Pad1)") (class "Default")
      (node (ref "X3") (pin "1") (pinfunction "VCTRL_1") (pintype "input"))
    )
    (net (code "177") (name "unconnected-(X4-VCTRL-Pad1)") (class "Default")
      (node (ref "X4") (pin "1") (pinfunction "VCTRL_1") (pintype "input"))
    )
    (net (code "178") (name "~{OPD_ENABLE}") (class "Default")
      (node (ref "D4") (pin "C") (pinfunction "C_C") (pintype "passive"))
      (node (ref "TP13") (pin "1") (pinfunction "1_1") (pintype "passive"))
      (node (ref "U1") (pin "3") (pinfunction "~{ON}_3") (pintype "input"))
      (node (ref "U7") (pin "28") (pinfunction "PB2_28") (pintype "bidirectional"))
    )
  )
)
